# microsmt_pnpboard_v17_sheet_1.net
KiCad netlist of a schematic drawn in Altium Designer
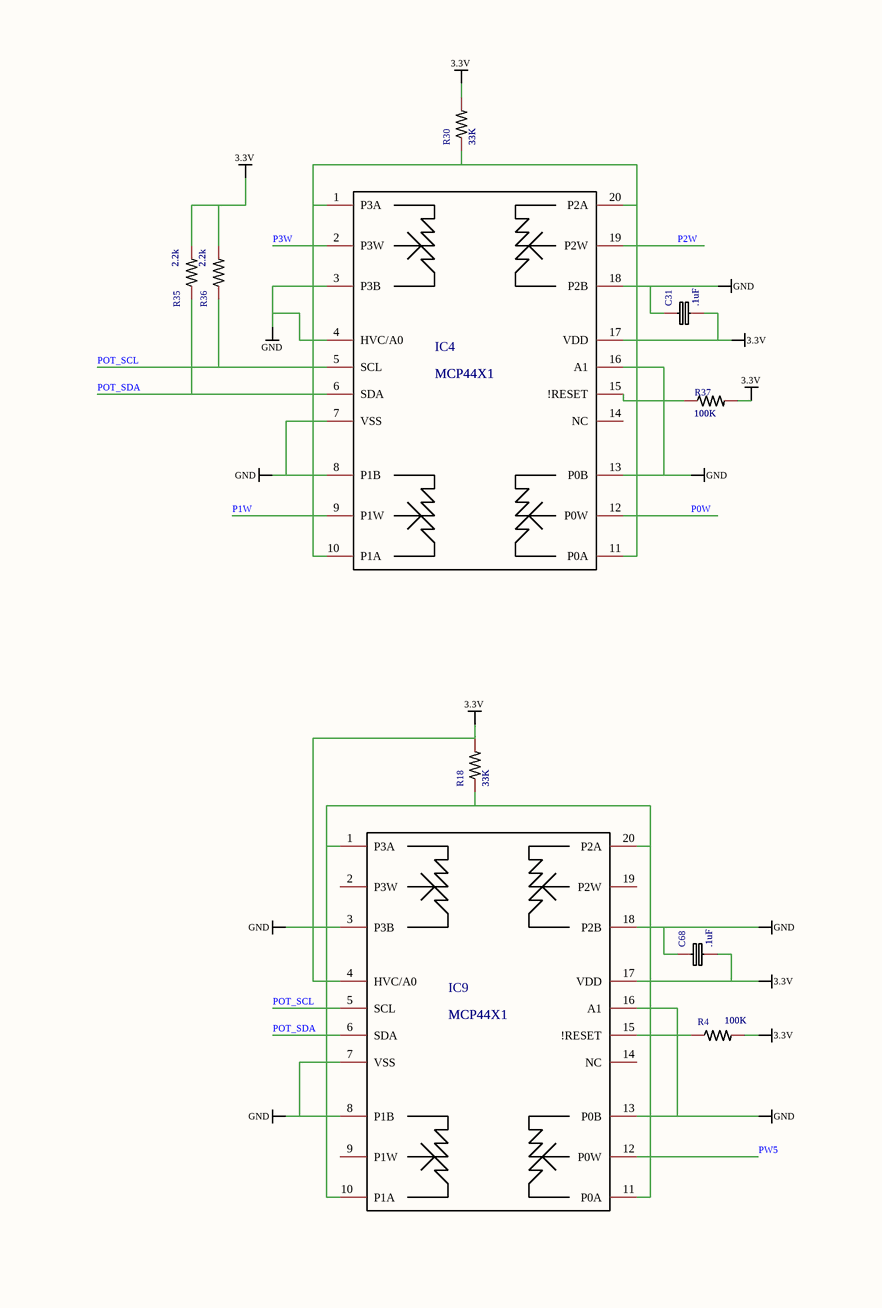
[diagram p0: microsmt_pnpboard_v17_sheet_1.schdoc, top middle]
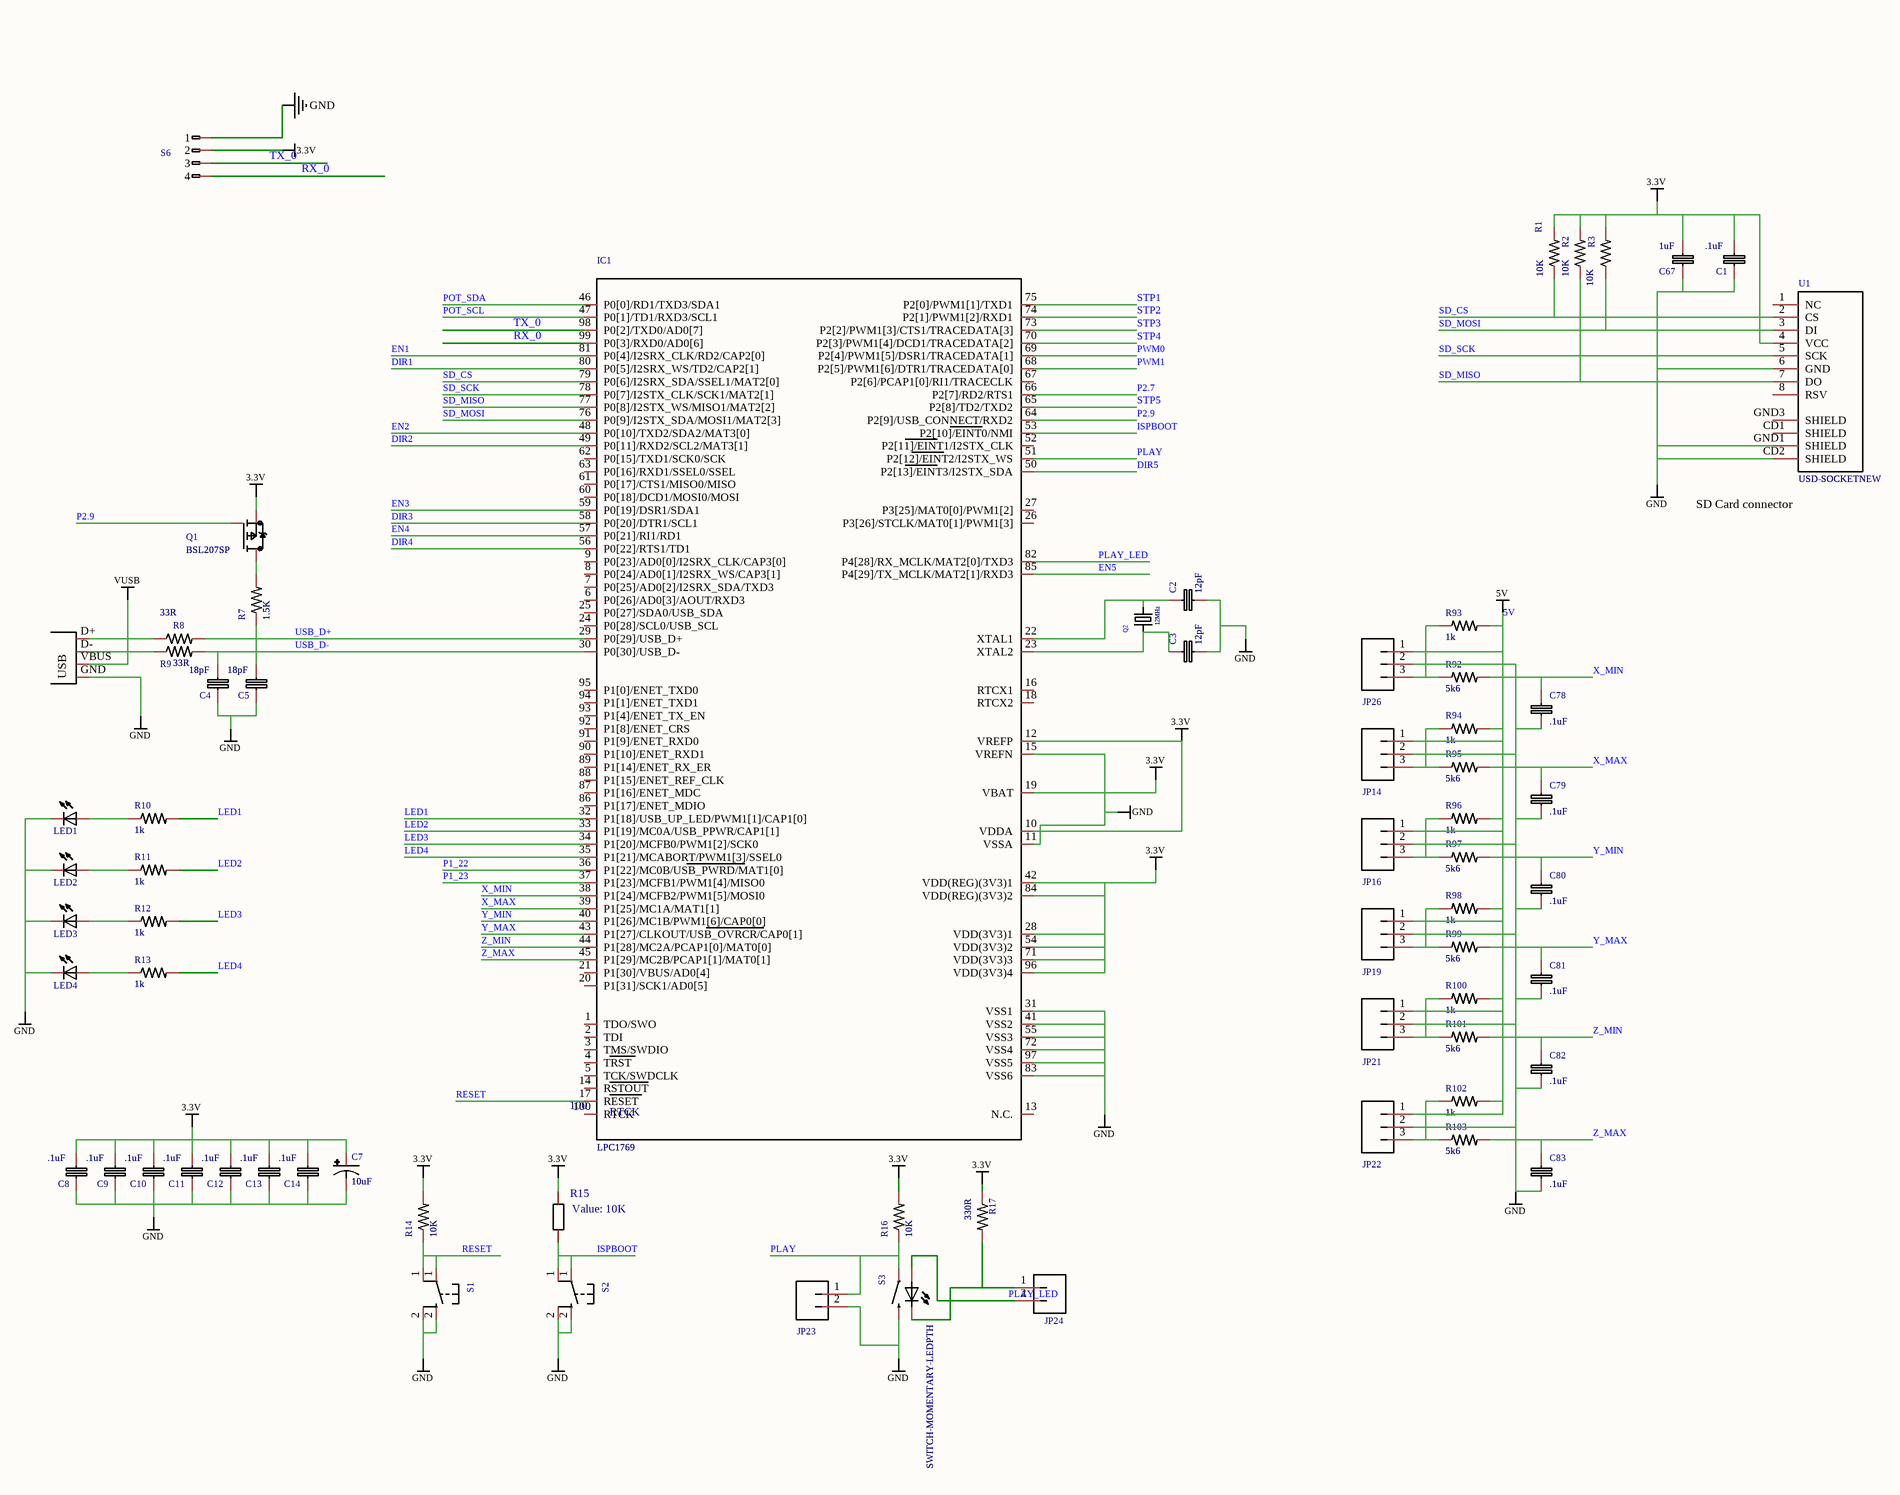
[diagram p1: microsmt_pnpboard_v17_sheet_1.schdoc, top right]
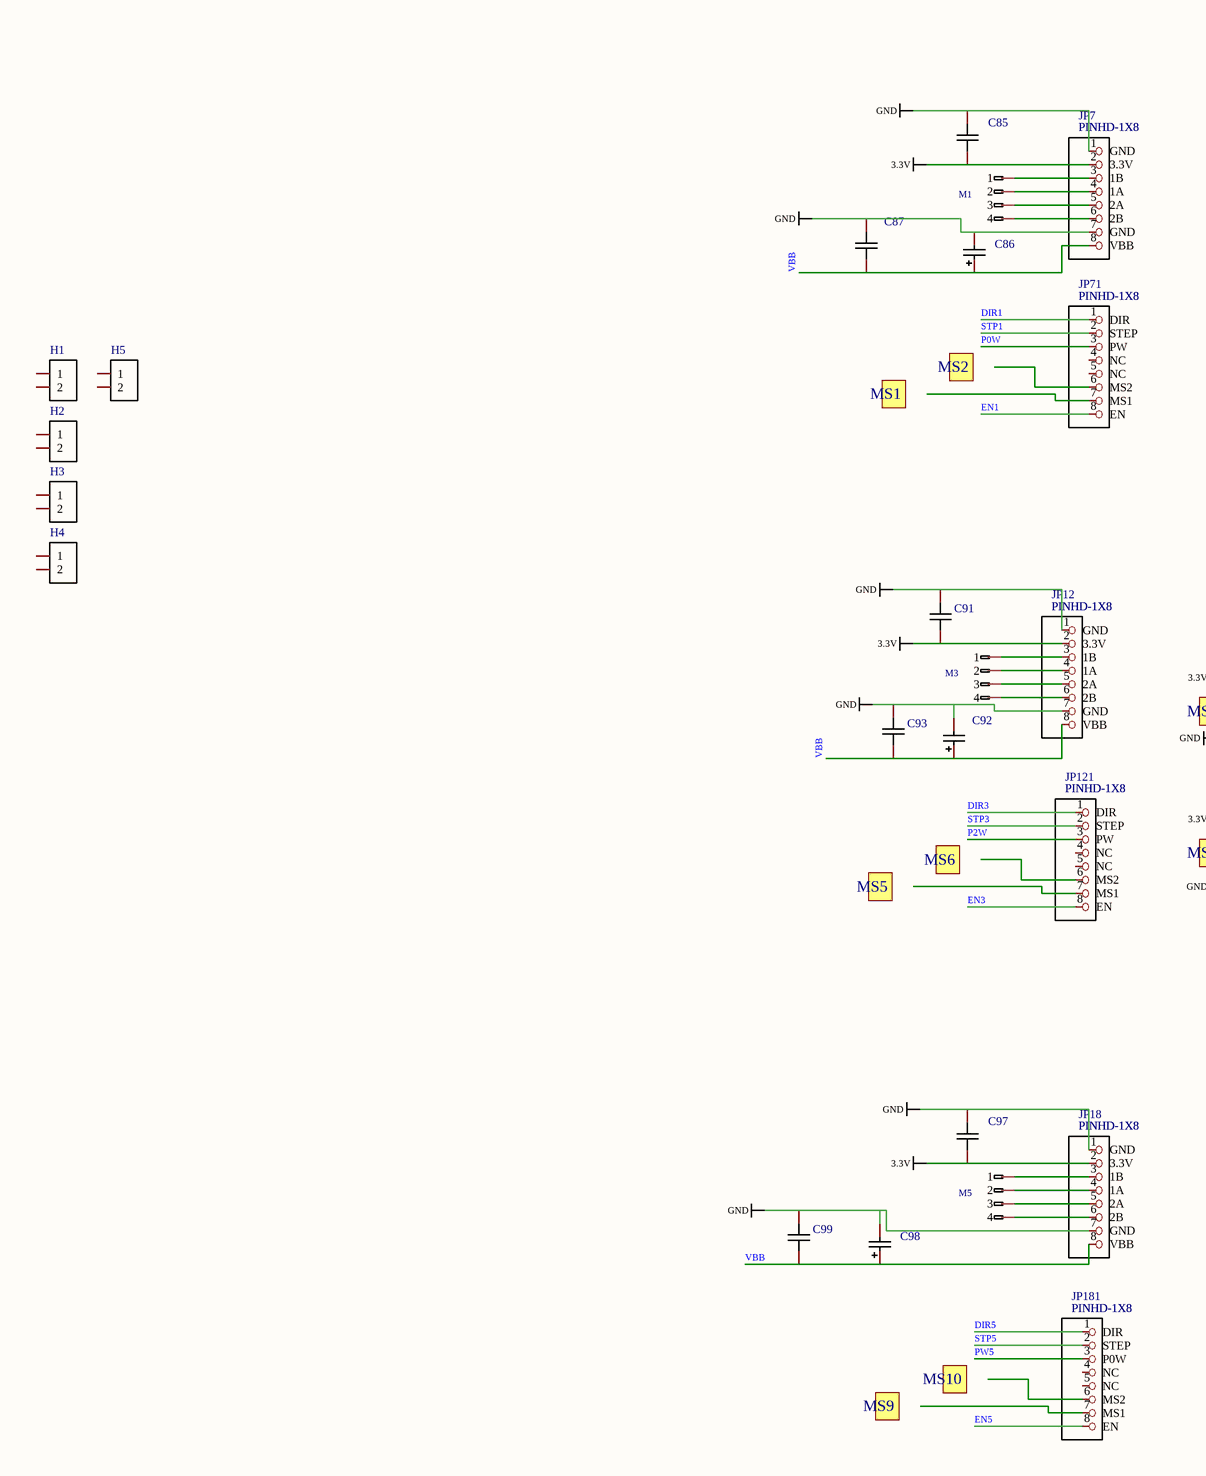
[diagram p2: microsmt_pnpboard_v17_sheet_1.schdoc, bottom left]
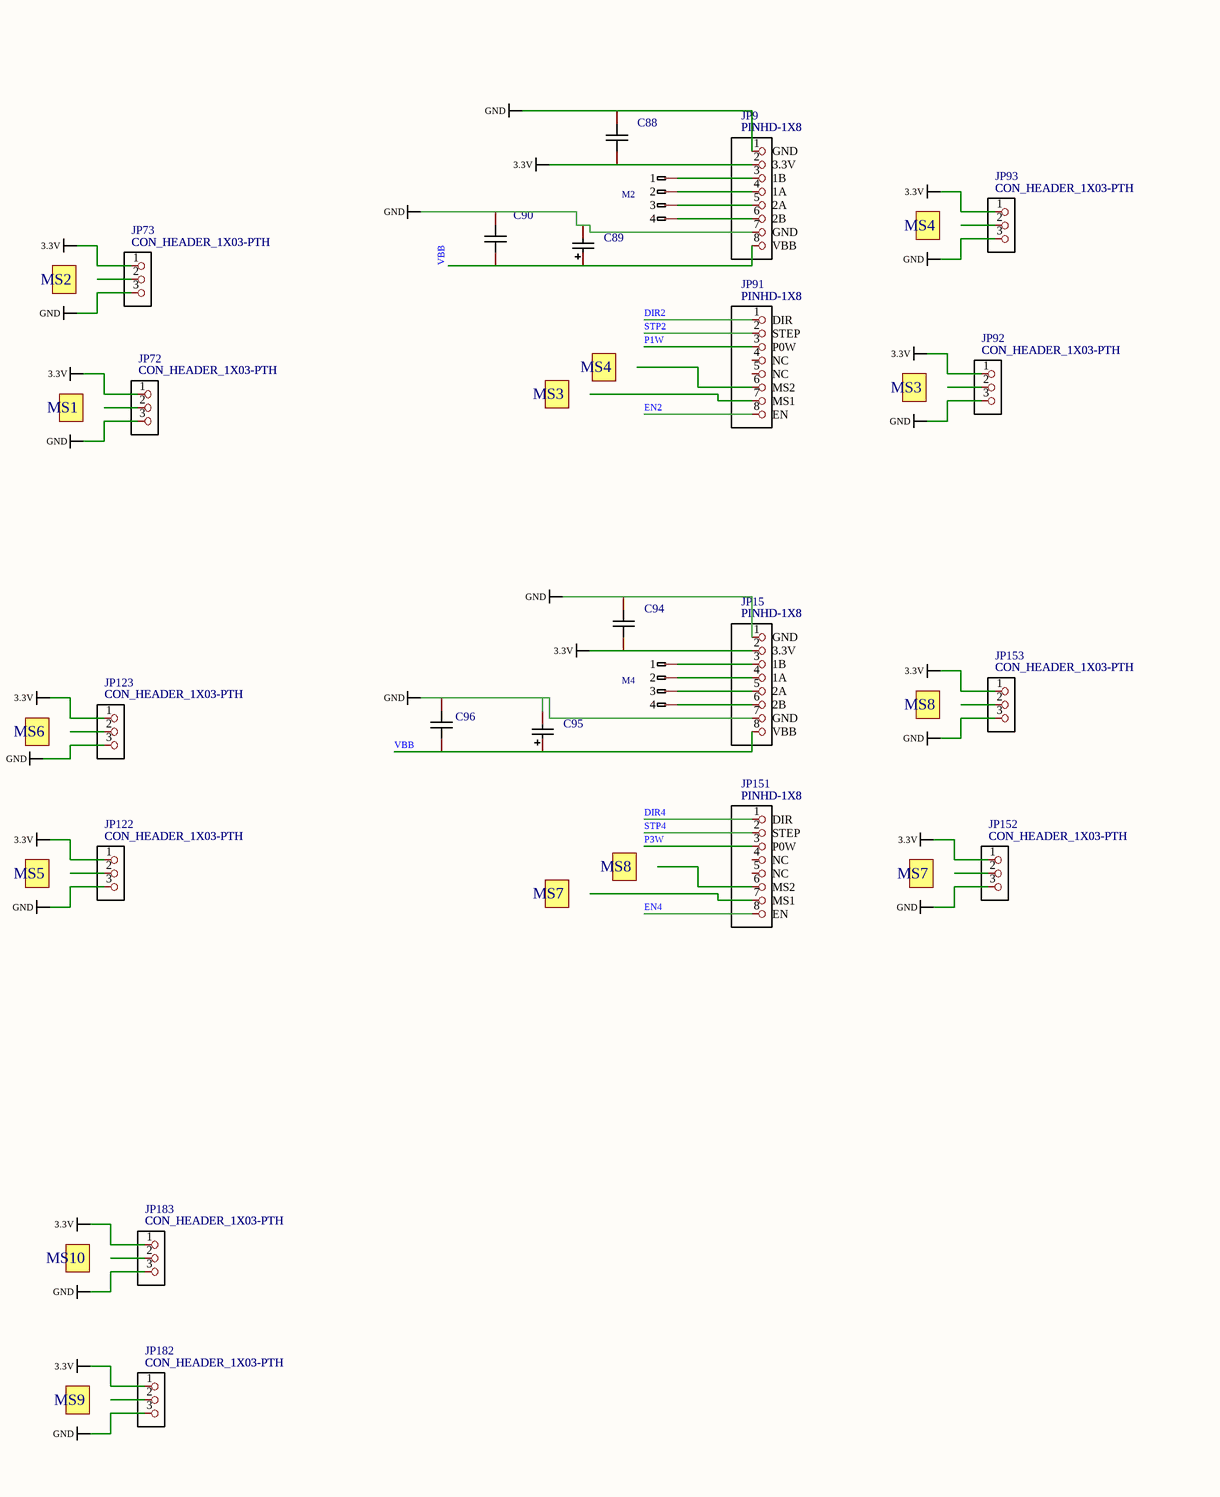
[diagram p3: microsmt_pnpboard_v17_sheet_1.schdoc, bottom middle]

(export (version "E")
  (design (tool "Eeschema 10.0.6"))
  (components
    (comp (ref "C1")
      (value ".1uF")
      (fields (field (name "NAME") ".1uF"))
      (libsource (lib "") (part "root_0_.1uF__2"))
    )
    (comp (ref "C2")
      (value "12pF")
      (fields (field (name "NAME") "12pF"))
      (libsource (lib "altium-import") (part "root_0_12pF_"))
    )
    (comp (ref "C3")
      (value "12pF")
      (fields (field (name "NAME") "12pF"))
      (libsource (lib "altium-import") (part "root_0_12pF_"))
    )
    (comp (ref "C4")
      (value "18pF")
      (fields (field (name "NAME") "18pF"))
      (libsource (lib "altium-import") (part "root_0_18pF_"))
    )
    (comp (ref "C5")
      (value "18pF")
      (fields (field (name "NAME") "18pF"))
      (libsource (lib "altium-import") (part "root_0_18pF_"))
    )
    (comp (ref "C7")
      (value "10uF")
      (fields (field (name "NAME") "10uF"))
      (libsource (lib "altium-import") (part "root_0_10uF_"))
    )
    (comp (ref "C8")
      (value ".1uF")
      (fields (field (name "NAME") ".1uF"))
      (libsource (lib "") (part "root_0_.1uF__1"))
    )
    (comp (ref "C9")
      (value ".1uF")
      (fields (field (name "NAME") ".1uF"))
      (libsource (lib "") (part "root_0_.1uF__1"))
    )
    (comp (ref "C10")
      (value ".1uF")
      (fields (field (name "NAME") ".1uF"))
      (libsource (lib "") (part "root_0_.1uF__1"))
    )
    (comp (ref "C11")
      (value ".1uF")
      (fields (field (name "NAME") ".1uF"))
      (libsource (lib "") (part "root_0_.1uF__1"))
    )
    (comp (ref "C12")
      (value ".1uF")
      (fields (field (name "NAME") ".1uF"))
      (libsource (lib "") (part "root_0_.1uF__1"))
    )
    (comp (ref "C13")
      (value ".1uF")
      (fields (field (name "NAME") ".1uF"))
      (libsource (lib "") (part "root_0_.1uF__1"))
    )
    (comp (ref "C14")
      (value ".1uF")
      (fields (field (name "NAME") ".1uF"))
      (libsource (lib "") (part "root_0_.1uF__1"))
    )
    (comp (ref "C31")
      (value ".1uF")
      (fields (field (name "NAME") ".1uF"))
      (libsource (lib "") (part "root_0_.1uF__3"))
    )
    (comp (ref "C67")
      (value "1uF")
      (fields (field (name "NAME") "1uF"))
      (libsource (lib "altium-import") (part "root_0_1uF_"))
    )
    (comp (ref "C68")
      (value ".1uF")
      (fields (field (name "NAME") ".1uF"))
      (libsource (lib "") (part "root_0_.1uF__3"))
    )
    (comp (ref "C78")
      (value ".1uF")
      (fields (field (name "NAME") ".1uF"))
      (libsource (lib "altium-import") (part "root_0_.1uF_"))
    )
    (comp (ref "C79")
      (value ".1uF")
      (fields (field (name "NAME") ".1uF"))
      (libsource (lib "altium-import") (part "root_0_.1uF_"))
    )
    (comp (ref "C80")
      (value ".1uF")
      (fields (field (name "NAME") ".1uF"))
      (libsource (lib "altium-import") (part "root_0_.1uF_"))
    )
    (comp (ref "C81")
      (value ".1uF")
      (fields (field (name "NAME") ".1uF"))
      (libsource (lib "altium-import") (part "root_0_.1uF_"))
    )
    (comp (ref "C82")
      (value ".1uF")
      (fields (field (name "NAME") ".1uF"))
      (libsource (lib "altium-import") (part "root_0_.1uF_"))
    )
    (comp (ref "C83")
      (value ".1uF")
      (fields (field (name "NAME") ".1uF"))
      (libsource (lib "altium-import") (part "root_0_.1uF_"))
    )
    (comp (ref "C85")
      (value "100nF")
      (description "容值:100nF;精度:±10%;额定电压:50V;温度系数:X7R;")
      (libsource (lib "altium-import") (part "root_1_CAP_0603_"))
    )
    (comp (ref "C86")
      (value "100uF")
      (description "容值:10uF;精度:±20%;额定电压:16V;电容体直径:-;电容体长度:-;纹波电流:-;等效串联电阻:-;工作寿命:2000hrs@85;工作温度:-40~+85;")
      (libsource (lib "altium-import") (part "root_3_C_Ele_SMD_3x5.4mm_"))
    )
    (comp (ref "C87")
      (value "100nF")
      (description "容值:100nF;精度:±10%;额定电压:50V;温度系数:X7R;")
      (libsource (lib "altium-import") (part "root_1_CAP_0603_"))
    )
    (comp (ref "C88")
      (value "100nF")
      (description "容值:100nF;精度:±10%;额定电压:50V;温度系数:X7R;")
      (libsource (lib "altium-import") (part "root_1_CAP_0603_"))
    )
    (comp (ref "C89")
      (value "100uF")
      (description "容值:10uF;精度:±20%;额定电压:16V;电容体直径:-;电容体长度:-;纹波电流:-;等效串联电阻:-;工作寿命:2000hrs@85;工作温度:-40~+85;")
      (libsource (lib "altium-import") (part "root_3_C_Ele_SMD_3x5.4mm_"))
    )
    (comp (ref "C90")
      (value "CAP_0603")
      (description "容值:100nF;精度:±10%;额定电压:50V;温度系数:X7R;")
      (libsource (lib "altium-import") (part "root_1_CAP_0603_"))
    )
    (comp (ref "C91")
      (value "CAP_0603")
      (description "容值:100nF;精度:±10%;额定电压:50V;温度系数:X7R;")
      (libsource (lib "altium-import") (part "root_1_CAP_0603_"))
    )
    (comp (ref "C92")
      (value "C_Ele_SMD_3x5.4mm")
      (description "容值:10uF;精度:±20%;额定电压:16V;电容体直径:-;电容体长度:-;纹波电流:-;等效串联电阻:-;工作寿命:2000hrs@85;工作温度:-40~+85;")
      (libsource (lib "altium-import") (part "root_3_C_Ele_SMD_3x5.4mm_"))
    )
    (comp (ref "C93")
      (value "100nF")
      (description "容值:100nF;精度:±10%;额定电压:50V;温度系数:X7R;")
      (libsource (lib "altium-import") (part "root_1_CAP_0603_"))
    )
    (comp (ref "C94")
      (value "100nF")
      (description "容值:100nF;精度:±10%;额定电压:50V;温度系数:X7R;")
      (libsource (lib "altium-import") (part "root_1_CAP_0603_"))
    )
    (comp (ref "C95")
      (value "100uF")
      (description "容值:10uF;精度:±20%;额定电压:16V;电容体直径:-;电容体长度:-;纹波电流:-;等效串联电阻:-;工作寿命:2000hrs@85;工作温度:-40~+85;")
      (libsource (lib "altium-import") (part "root_3_C_Ele_SMD_3x5.4mm_"))
    )
    (comp (ref "C96")
      (value "100nF")
      (description "容值:100nF;精度:±10%;额定电压:50V;温度系数:X7R;")
      (libsource (lib "altium-import") (part "root_1_CAP_0603_"))
    )
    (comp (ref "C97")
      (value "100nF")
      (description "容值:100nF;精度:±10%;额定电压:50V;温度系数:X7R;")
      (libsource (lib "altium-import") (part "root_1_CAP_0603_"))
    )
    (comp (ref "C98")
      (value "100uF")
      (description "容值:10uF;精度:±20%;额定电压:16V;电容体直径:-;电容体长度:-;纹波电流:-;等效串联电阻:-;工作寿命:2000hrs@85;工作温度:-40~+85;")
      (libsource (lib "altium-import") (part "root_3_C_Ele_SMD_3x5.4mm_"))
    )
    (comp (ref "C99")
      (value "100nF")
      (description "容值:100nF;精度:±10%;额定电压:50V;温度系数:X7R;")
      (libsource (lib "altium-import") (part "root_1_CAP_0603_"))
    )
    (comp (ref "H1")
      (value "HDR-F_2.54_1x2P")
      (libsource (lib "altium-import") (part "root_0_HDR-F_2.54_1x2P_"))
    )
    (comp (ref "H2")
      (value "HDR-F_2.54_1x2P")
      (libsource (lib "altium-import") (part "root_0_HDR-F_2.54_1x2P_"))
    )
    (comp (ref "H3")
      (value "HDR-F_2.54_1x2P")
      (libsource (lib "altium-import") (part "root_0_HDR-F_2.54_1x2P_"))
    )
    (comp (ref "H4")
      (value "HDR-F_2.54_1x2P")
      (libsource (lib "altium-import") (part "root_0_HDR-F_2.54_1x2P_"))
    )
    (comp (ref "H5")
      (value "HDR-F_2.54_1x2P")
      (libsource (lib "altium-import") (part "root_0_HDR-F_2.54_1x2P_"))
    )
    (comp (ref "IC1")
      (value "LPC1769")
      (fields (field (name "NAME") "LPC1769") (field (name "NAME_1") "RTCK") (field (name "NUMBER") "100"))
      (libsource (lib "altium-import") (part "root_0_LPC1769_"))
    )
    (comp (ref "IC4")
      (value "MCP44X1")
      (fields (field (name "NAME") "MCP44X1"))
      (libsource (lib "altium-import") (part "root_0_MCP44X1_"))
    )
    (comp (ref "IC9")
      (value "MCP44X1")
      (fields (field (name "NAME") "MCP44X1"))
      (libsource (lib "altium-import") (part "root_0_MCP44X1_"))
    )
    (comp (ref "JP7")
      (value "PINHD-1X8")
      (fields (field (name "NAME") "PINHD-1X8"))
      (libsource (lib "altium-import") (part "root_0_PINHD-1X8_"))
    )
    (comp (ref "JP9")
      (value "PINHD-1X8")
      (fields (field (name "NAME") "PINHD-1X8"))
      (libsource (lib "altium-import") (part "root_0_PINHD-1X8_"))
    )
    (comp (ref "JP12")
      (value "PINHD-1X8")
      (fields (field (name "NAME") "PINHD-1X8"))
      (libsource (lib "altium-import") (part "root_0_PINHD-1X8_"))
    )
    (comp (ref "JP14") (value "M03POLAR") (libsource (lib "altium-import") (part "root_0_M03POLAR_")))
    (comp (ref "JP15")
      (value "PINHD-1X8")
      (fields (field (name "NAME") "PINHD-1X8"))
      (libsource (lib "altium-import") (part "root_0_PINHD-1X8_"))
    )
    (comp (ref "JP16") (value "M03POLAR") (libsource (lib "altium-import") (part "root_0_M03POLAR_")))
    (comp (ref "JP18")
      (value "PINHD-1X8")
      (fields (field (name "NAME") "PINHD-1X8"))
      (libsource (lib "altium-import") (part "root_0_PINHD-1X8_"))
    )
    (comp (ref "JP19") (value "M03POLAR") (libsource (lib "altium-import") (part "root_0_M03POLAR_")))
    (comp (ref "JP21") (value "M03POLAR") (libsource (lib "altium-import") (part "root_0_M03POLAR_")))
    (comp (ref "JP22") (value "M03POLAR") (libsource (lib "altium-import") (part "root_0_M03POLAR_")))
    (comp (ref "JP23") (value "M02PTH") (libsource (lib "") (part "root_0_M02PTH__1")))
    (comp (ref "JP24") (value "M02PTH") (libsource (lib "altium-import") (part "root_0_M02PTH_")))
    (comp (ref "JP26") (value "M03POLAR") (libsource (lib "altium-import") (part "root_0_M03POLAR_")))
    (comp (ref "JP71")
      (value "PINHD-1X8")
      (fields (field (name "NAME") "PINHD-1X8"))
      (libsource (lib "altium-import") (part "root_0_PINHD-1X8_"))
    )
    (comp (ref "JP72")
      (value "CON_HEADER_1X03-PTH")
      (fields (field (name "NAME") "CON_HEADER_1X03-PTH"))
      (libsource (lib "altium-import") (part "root_0_CON_HEADER_1X03-PTH_"))
    )
    (comp (ref "JP73")
      (value "CON_HEADER_1X03-PTH")
      (fields (field (name "NAME") "CON_HEADER_1X03-PTH"))
      (libsource (lib "altium-import") (part "root_0_CON_HEADER_1X03-PTH_"))
    )
    (comp (ref "JP91")
      (value "PINHD-1X8")
      (fields (field (name "NAME") "PINHD-1X8"))
      (libsource (lib "altium-import") (part "root_0_PINHD-1X8_"))
    )
    (comp (ref "JP92")
      (value "CON_HEADER_1X03-PTH")
      (fields (field (name "NAME") "CON_HEADER_1X03-PTH"))
      (libsource (lib "altium-import") (part "root_0_CON_HEADER_1X03-PTH_"))
    )
    (comp (ref "JP93")
      (value "CON_HEADER_1X03-PTH")
      (fields (field (name "NAME") "CON_HEADER_1X03-PTH"))
      (libsource (lib "altium-import") (part "root_0_CON_HEADER_1X03-PTH_"))
    )
    (comp (ref "JP121")
      (value "PINHD-1X8")
      (fields (field (name "NAME") "PINHD-1X8"))
      (libsource (lib "altium-import") (part "root_0_PINHD-1X8_"))
    )
    (comp (ref "JP122")
      (value "CON_HEADER_1X03-PTH")
      (fields (field (name "NAME") "CON_HEADER_1X03-PTH"))
      (libsource (lib "altium-import") (part "root_0_CON_HEADER_1X03-PTH_"))
    )
    (comp (ref "JP123")
      (value "CON_HEADER_1X03-PTH")
      (fields (field (name "NAME") "CON_HEADER_1X03-PTH"))
      (libsource (lib "altium-import") (part "root_0_CON_HEADER_1X03-PTH_"))
    )
    (comp (ref "JP151")
      (value "PINHD-1X8")
      (fields (field (name "NAME") "PINHD-1X8"))
      (libsource (lib "altium-import") (part "root_0_PINHD-1X8_"))
    )
    (comp (ref "JP152")
      (value "CON_HEADER_1X03-PTH")
      (fields (field (name "NAME") "CON_HEADER_1X03-PTH"))
      (libsource (lib "altium-import") (part "root_0_CON_HEADER_1X03-PTH_"))
    )
    (comp (ref "JP153")
      (value "CON_HEADER_1X03-PTH")
      (fields (field (name "NAME") "CON_HEADER_1X03-PTH"))
      (libsource (lib "altium-import") (part "root_0_CON_HEADER_1X03-PTH_"))
    )
    (comp (ref "JP181")
      (value "PINHD-1X8")
      (fields (field (name "NAME") "PINHD-1X8"))
      (libsource (lib "altium-import") (part "root_0_PINHD-1X8_"))
    )
    (comp (ref "JP182")
      (value "CON_HEADER_1X03-PTH")
      (fields (field (name "NAME") "CON_HEADER_1X03-PTH"))
      (libsource (lib "altium-import") (part "root_0_CON_HEADER_1X03-PTH_"))
    )
    (comp (ref "JP183")
      (value "CON_HEADER_1X03-PTH")
      (fields (field (name "NAME") "CON_HEADER_1X03-PTH"))
      (libsource (lib "altium-import") (part "root_0_CON_HEADER_1X03-PTH_"))
    )
    (comp (ref "LED1")
      (value "LEDCHIP-LED0805")
      (libsource (lib "altium-import") (part "root_0_LEDCHIP-LED0805_"))
    )
    (comp (ref "LED2")
      (value "LEDCHIP-LED0805")
      (libsource (lib "altium-import") (part "root_0_LEDCHIP-LED0805_"))
    )
    (comp (ref "LED3")
      (value "LEDCHIP-LED0805")
      (libsource (lib "altium-import") (part "root_0_LEDCHIP-LED0805_"))
    )
    (comp (ref "LED4")
      (value "LEDCHIP-LED0805")
      (libsource (lib "altium-import") (part "root_0_LEDCHIP-LED0805_"))
    )
    (comp (ref "M1") (value "10X04MTA") (libsource (lib "altium-import") (part "root_0_10X04MTA_")))
    (comp (ref "M2") (value "10X04MTA") (libsource (lib "altium-import") (part "root_0_10X04MTA_")))
    (comp (ref "M3") (value "10X04MTA") (libsource (lib "altium-import") (part "root_0_10X04MTA_")))
    (comp (ref "M4") (value "10X04MTA") (libsource (lib "altium-import") (part "root_0_10X04MTA_")))
    (comp (ref "M5") (value "10X04MTA") (libsource (lib "altium-import") (part "root_0_10X04MTA_")))
    (comp (ref "Q1")
      (value "BSL207SP")
      (fields (field (name "NAME") "BSL207SP"))
      (libsource (lib "altium-import") (part "root_0_BSL207SP_"))
    )
    (comp (ref "Q2")
      (value "12MHz")
      (fields (field (name "NAME") "12MHz"))
      (libsource (lib "altium-import") (part "root_0_12MHz_"))
    )
    (comp (ref "R1")
      (value "10K")
      (fields (field (name "NAME") "10K"))
      (libsource (lib "altium-import") (part "root_0_10K_"))
    )
    (comp (ref "R2")
      (value "10K")
      (fields (field (name "NAME") "10K"))
      (libsource (lib "altium-import") (part "root_0_10K_"))
    )
    (comp (ref "R3")
      (value "10K")
      (fields (field (name "NAME") "10K"))
      (libsource (lib "altium-import") (part "root_0_10K_"))
    )
    (comp (ref "R4")
      (value "100K")
      (fields (field (name "NAME") "100K"))
      (libsource (lib "altium-import") (part "root_0_100K_"))
    )
    (comp (ref "R7")
      (value "1.5K")
      (fields (field (name "NAME") "1.5K"))
      (libsource (lib "altium-import") (part "root_0_1.5K_"))
    )
    (comp (ref "R8")
      (value "33R")
      (fields (field (name "NAME") "33R"))
      (libsource (lib "altium-import") (part "root_0_33R_"))
    )
    (comp (ref "R9")
      (value "33R")
      (fields (field (name "NAME") "33R"))
      (libsource (lib "altium-import") (part "root_0_33R_"))
    )
    (comp (ref "R10")
      (value "1k")
      (fields (field (name "NAME") "1k"))
      (libsource (lib "altium-import") (part "root_0_1k_"))
    )
    (comp (ref "R11")
      (value "1k")
      (fields (field (name "NAME") "1k"))
      (libsource (lib "altium-import") (part "root_0_1k_"))
    )
    (comp (ref "R12")
      (value "1k")
      (fields (field (name "NAME") "1k"))
      (libsource (lib "altium-import") (part "root_0_1k_"))
    )
    (comp (ref "R13")
      (value "1k")
      (fields (field (name "NAME") "1k"))
      (libsource (lib "altium-import") (part "root_0_1k_"))
    )
    (comp (ref "R14")
      (value "10K")
      (fields (field (name "NAME") "10K"))
      (libsource (lib "altium-import") (part "root_0_10K_"))
    )
    (comp (ref "R15")
      (value "10K")
      (fields (field (name "Comment") "Res_0603"))
      (libsource (lib "altium-import") (part "root_1_Res_0603_"))
    )
    (comp (ref "R16")
      (value "10K")
      (fields (field (name "NAME") "10K"))
      (libsource (lib "altium-import") (part "root_0_10K_"))
    )
    (comp (ref "R17")
      (value "330R")
      (fields (field (name "NAME") "330R"))
      (libsource (lib "altium-import") (part "root_0_330R_"))
    )
    (comp (ref "R18")
      (value "33K")
      (fields (field (name "NAME") "33K"))
      (libsource (lib "altium-import") (part "root_0_33K_"))
    )
    (comp (ref "R30")
      (value "33K")
      (fields (field (name "NAME") "33K"))
      (libsource (lib "altium-import") (part "root_0_33K_"))
    )
    (comp (ref "R35")
      (value "2.2k")
      (fields (field (name "NAME") "2.2k"))
      (libsource (lib "altium-import") (part "root_0_2.2k_"))
    )
    (comp (ref "R36")
      (value "2.2k")
      (fields (field (name "NAME") "2.2k"))
      (libsource (lib "altium-import") (part "root_0_2.2k_"))
    )
    (comp (ref "R37")
      (value "100K")
      (fields (field (name "NAME") "100K"))
      (libsource (lib "altium-import") (part "root_3_100K_"))
    )
    (comp (ref "R92")
      (value "5k6")
      (fields (field (name "NAME") "5k6"))
      (libsource (lib "altium-import") (part "root_0_5k6_"))
    )
    (comp (ref "R93")
      (value "1k")
      (fields (field (name "NAME") "1k"))
      (libsource (lib "altium-import") (part "root_0_1k_"))
    )
    (comp (ref "R94")
      (value "1k")
      (fields (field (name "NAME") "1k"))
      (libsource (lib "altium-import") (part "root_0_1k_"))
    )
    (comp (ref "R95")
      (value "5k6")
      (fields (field (name "NAME") "5k6"))
      (libsource (lib "altium-import") (part "root_0_5k6_"))
    )
    (comp (ref "R96")
      (value "1k")
      (fields (field (name "NAME") "1k"))
      (libsource (lib "altium-import") (part "root_0_1k_"))
    )
    (comp (ref "R97")
      (value "5k6")
      (fields (field (name "NAME") "5k6"))
      (libsource (lib "altium-import") (part "root_0_5k6_"))
    )
    (comp (ref "R98")
      (value "1k")
      (fields (field (name "NAME") "1k"))
      (libsource (lib "altium-import") (part "root_0_1k_"))
    )
    (comp (ref "R99")
      (value "5k6")
      (fields (field (name "NAME") "5k6"))
      (libsource (lib "altium-import") (part "root_0_5k6_"))
    )
    (comp (ref "R100")
      (value "1k")
      (fields (field (name "NAME") "1k"))
      (libsource (lib "altium-import") (part "root_0_1k_"))
    )
    (comp (ref "R101")
      (value "5k6")
      (fields (field (name "NAME") "5k6"))
      (libsource (lib "altium-import") (part "root_0_5k6_"))
    )
    (comp (ref "R102")
      (value "1k")
      (fields (field (name "NAME") "1k"))
      (libsource (lib "altium-import") (part "root_0_1k_"))
    )
    (comp (ref "R103")
      (value "5k6")
      (fields (field (name "NAME") "5k6"))
      (libsource (lib "altium-import") (part "root_0_5k6_"))
    )
    (comp (ref "S1") (value "TAC_SWITCHSMD") (libsource (lib "altium-import") (part "root_0_TAC_SWITCHSMD_")))
    (comp (ref "S2") (value "TAC_SWITCHSMD") (libsource (lib "altium-import") (part "root_0_TAC_SWITCHSMD_")))
    (comp (ref "S3")
      (value "SWITCH-MOMENTARY-LEDPTH")
      (fields (field (name "NAME") "SWITCH-MOMENTARY-LEDPTH"))
      (libsource (lib "altium-import") (part "root_0_SWITCH-MOMENTARY-LEDPTH_"))
    )
    (comp (ref "S6") (value "10X04MTA") (libsource (lib "altium-import") (part "root_0_10X04MTA_")))
    (comp (ref "U1")
      (value "USD-SOCKETNEW")
      (fields (field (name "NAME") "USD-SOCKETNEW"))
      (libsource (lib "altium-import") (part "root_0_USD-SOCKETNEW_"))
    )
    (comp (ref "X14") (value "USBPTH") (libsource (lib "altium-import") (part "root_0_USBPTH_")))
  )
  (nets
    (net (code "1") (name "/DIR1") (class "Default")
      (node (ref "IC1") (pin "80") (pinfunction "P0[5]/I2SRX_WS/TD2/CAP2[1]_80") (pintype "passive"))
      (node (ref "JP71") (pin "1") (pinfunction "GND_1") (pintype "passive"))
    )
    (net (code "2") (name "/DIR2") (class "Default")
      (node (ref "IC1") (pin "49") (pinfunction "P0[11]/RXD2/SCL2/MAT3[1]_49") (pintype "passive"))
      (node (ref "JP91") (pin "1") (pinfunction "GND_1") (pintype "passive"))
    )
    (net (code "3") (name "/DIR3") (class "Default")
      (node (ref "IC1") (pin "58") (pinfunction "P0[20]/DTR1/SCL1_58") (pintype "passive"))
      (node (ref "JP121") (pin "1") (pinfunction "GND_1") (pintype "passive"))
    )
    (net (code "4") (name "/DIR4") (class "Default")
      (node (ref "IC1") (pin "56") (pinfunction "P0[22]/RTS1/TD1_56") (pintype "passive"))
      (node (ref "JP151") (pin "1") (pinfunction "GND_1") (pintype "passive"))
    )
    (net (code "5") (name "/DIR5") (class "Default")
      (node (ref "IC1") (pin "50") (pinfunction "P2[13]/EINT3/I2STX_SDA_50") (pintype "passive"))
      (node (ref "JP181") (pin "1") (pinfunction "GND_1") (pintype "passive"))
    )
    (net (code "6") (name "/EN1") (class "Default")
      (node (ref "IC1") (pin "81") (pinfunction "P0[4]/I2SRX_CLK/RD2/CAP2[0]_81") (pintype "passive"))
      (node (ref "JP71") (pin "8") (pinfunction "VBB_8") (pintype "passive"))
    )
    (net (code "7") (name "/EN2") (class "Default")
      (node (ref "IC1") (pin "48") (pinfunction "P0[10]/TXD2/SDA2/MAT3[0]_48") (pintype "passive"))
      (node (ref "JP91") (pin "8") (pinfunction "VBB_8") (pintype "passive"))
    )
    (net (code "8") (name "/EN3") (class "Default")
      (node (ref "IC1") (pin "59") (pinfunction "P0[19]/DSR1/SDA1_59") (pintype "passive"))
      (node (ref "JP121") (pin "8") (pinfunction "VBB_8") (pintype "passive"))
    )
    (net (code "9") (name "/EN4") (class "Default")
      (node (ref "IC1") (pin "57") (pinfunction "P0[21]/RI1/RD1_57") (pintype "passive"))
      (node (ref "JP151") (pin "8") (pinfunction "VBB_8") (pintype "passive"))
    )
    (net (code "10") (name "/EN5") (class "Default")
      (node (ref "IC1") (pin "85") (pinfunction "P4[29]/TX_MCLK/MAT2[1]/RXD3_85") (pintype "passive"))
      (node (ref "JP181") (pin "8") (pinfunction "VBB_8") (pintype "passive"))
    )
    (net (code "11") (name "/ISPBOOT") (class "Default")
      (node (ref "IC1") (pin "53") (pinfunction "P2[10]/EINT0/NMI_53") (pintype "passive"))
      (node (ref "R15") (pin "1") (pinfunction "1_1") (pintype "passive"))
      (node (ref "S2") (pin "1") (pinfunction "1_1") (pintype "passive"))
    )
    (net (code "12") (name "/LED1") (class "Default")
      (node (ref "IC1") (pin "32") (pinfunction "P1[18]/USB_UP_LED/PWM1[1]/CAP1[0]_32") (pintype "passive"))
      (node (ref "R10") (pin "2") (pinfunction "2_2") (pintype "passive"))
    )
    (net (code "13") (name "/LED2") (class "Default")
      (node (ref "IC1") (pin "33") (pinfunction "P1[19]/MC0A/USB_PPWR/CAP1[1]_33") (pintype "passive"))
      (node (ref "R11") (pin "2") (pinfunction "2_2") (pintype "passive"))
    )
    (net (code "14") (name "/LED3") (class "Default")
      (node (ref "IC1") (pin "34") (pinfunction "P1[20]/MCFB0/PWM1[2]/SCK0_34") (pintype "passive"))
      (node (ref "R12") (pin "2") (pinfunction "2_2") (pintype "passive"))
    )
    (net (code "15") (name "/LED4") (class "Default")
      (node (ref "IC1") (pin "35") (pinfunction "P1[21]/MCABORT/PWM1[3]/SSEL0_35") (pintype "passive"))
      (node (ref "R13") (pin "2") (pinfunction "2_2") (pintype "passive"))
    )
    (net (code "26") (name "/P0W") (class "Default")
      (node (ref "IC4") (pin "12") (pinfunction "P0W_12") (pintype "passive"))
      (node (ref "JP71") (pin "3") (pinfunction "1B_3") (pintype "passive"))
    )
    (net (code "27") (name "/P1W") (class "Default")
      (node (ref "IC4") (pin "9") (pinfunction "P1W_9") (pintype "passive"))
      (node (ref "JP91") (pin "3") (pinfunction "1B_3") (pintype "passive"))
    )
    (net (code "28") (name "/P1_22") (class "Default")
      (node (ref "IC1") (pin "36") (pinfunction "P1[22]/MC0B/USB_PWRD/MAT1[0]_36") (pintype "passive"))
    )
    (net (code "29") (name "/P1_23") (class "Default")
      (node (ref "IC1") (pin "37") (pinfunction "P1[23]/MCFB1/PWM1[4]/MISO0_37") (pintype "passive"))
    )
    (net (code "30") (name "/P2.7") (class "Default")
      (node (ref "IC1") (pin "66") (pinfunction "P2[7]/RD2/RTS1_66") (pintype "passive"))
    )
    (net (code "31") (name "/P2.9") (class "Default")
      (node (ref "IC1") (pin "64") (pinfunction "P2[9]/USB_CONNECT/RXD2_64") (pintype "passive"))
      (node (ref "Q1") (pin "3") (pinfunction "G_3") (pintype "passive"))
    )
    (net (code "32") (name "/P2W") (class "Default")
      (node (ref "IC4") (pin "19") (pinfunction "P2W_19") (pintype "passive"))
      (node (ref "JP121") (pin "3") (pinfunction "1B_3") (pintype "passive"))
    )
    (net (code "33") (name "/P3W") (class "Default")
      (node (ref "IC4") (pin "2") (pinfunction "P3W_2") (pintype "passive"))
      (node (ref "JP151") (pin "3") (pinfunction "1B_3") (pintype "passive"))
    )
    (net (code "34") (name "/PLAY") (class "Default")
      (node (ref "IC1") (pin "51") (pinfunction "P2[12]/EINT2/I2STX_WS_51") (pintype "passive"))
      (node (ref "JP23") (pin "1") (pinfunction "1_1") (pintype "passive"))
      (node (ref "R16") (pin "1") (pinfunction "1_1") (pintype "passive"))
      (node (ref "S3") (pin "4") (pinfunction "1_4") (pintype "passive"))
    )
    (net (code "35") (name "/PLAY_LED") (class "Default")
      (node (ref "IC1") (pin "82") (pinfunction "P4[28]/RX_MCLK/MAT2[0]/TXD3_82") (pintype "passive"))
      (node (ref "JP24") (pin "2") (pinfunction "2_2") (pintype "passive"))
      (node (ref "S3") (pin "A") (pinfunction "A_A") (pintype "passive"))
    )
    (net (code "36") (name "/POT_SCL") (class "Default")
      (node (ref "IC1") (pin "47") (pinfunction "P0[1]/TD1/RXD3/SCL1_47") (pintype "passive"))
      (node (ref "IC4") (pin "5") (pinfunction "SCL_5") (pintype "passive"))
      (node (ref "IC9") (pin "5") (pinfunction "SCL_5") (pintype "passive"))
      (node (ref "R36") (pin "1") (pinfunction "1_1") (pintype "passive"))
    )
    (net (code "37") (name "/POT_SDA") (class "Default")
      (node (ref "IC1") (pin "46") (pinfunction "P0[0]/RD1/TXD3/SDA1_46") (pintype "passive"))
      (node (ref "IC4") (pin "6") (pinfunction "SDA_6") (pintype "passive"))
      (node (ref "IC9") (pin "6") (pinfunction "SDA_6") (pintype "passive"))
      (node (ref "R35") (pin "1") (pinfunction "1_1") (pintype "passive"))
    )
    (net (code "38") (name "/PW5") (class "Default")
      (node (ref "IC9") (pin "12") (pinfunction "P0W_12") (pintype "passive"))
      (node (ref "JP181") (pin "3") (pinfunction "1B_3") (pintype "passive"))
    )
    (net (code "39") (name "/PWM0") (class "Default")
      (node (ref "IC1") (pin "69") (pinfunction "P2[4]/PWM1[5]/DSR1/TRACEDATA[1]_69") (pintype "passive"))
    )
    (net (code "40") (name "/PWM1") (class "Default")
      (node (ref "IC1") (pin "68") (pinfunction "P2[5]/PWM1[6]/DTR1/TRACEDATA[0]_68") (pintype "passive"))
    )
    (net (code "41") (name "/RESET") (class "Default")
      (node (ref "IC1") (pin "17") (pinfunction "RESET_17") (pintype "passive"))
      (node (ref "R14") (pin "1") (pinfunction "1_1") (pintype "passive"))
      (node (ref "S1") (pin "1") (pinfunction "1_1") (pintype "passive"))
    )
    (net (code "42") (name "/RX_0") (class "Default")
      (node (ref "IC1") (pin "99") (pinfunction "P0[3]/RXD0/AD0[6]_99") (pintype "passive"))
      (node (ref "S6") (pin "4") (pinfunction "4_4") (pintype "passive"))
    )
    (net (code "43") (name "/SD_CS") (class "Default")
      (node (ref "IC1") (pin "79") (pinfunction "P0[6]/I2SRX_SDA/SSEL1/MAT2[0]_79") (pintype "passive"))
      (node (ref "R1") (pin "1") (pinfunction "1_1") (pintype "passive"))
      (node (ref "U1") (pin "2") (pinfunction "CS_2") (pintype "passive"))
    )
    (net (code "44") (name "/SD_MISO") (class "Default")
      (node (ref "IC1") (pin "77") (pinfunction "P0[8]/I2STX_WS/MISO1/MAT2[2]_77") (pintype "passive"))
      (node (ref "R2") (pin "1") (pinfunction "1_1") (pintype "passive"))
      (node (ref "U1") (pin "7") (pinfunction "DO_7") (pintype "passive"))
    )
    (net (code "45") (name "/SD_MOSI") (class "Default")
      (node (ref "IC1") (pin "76") (pinfunction "P0[9]/I2STX_SDA/MOSI1/MAT2[3]_76") (pintype "passive"))
      (node (ref "R3") (pin "1") (pinfunction "1_1") (pintype "passive"))
      (node (ref "U1") (pin "3") (pinfunction "DI_3") (pintype "passive"))
    )
    (net (code "46") (name "/SD_SCK") (class "Default")
      (node (ref "IC1") (pin "78") (pinfunction "P0[7]/I2STX_CLK/SCK1/MAT2[1]_78") (pintype "passive"))
      (node (ref "U1") (pin "5") (pinfunction "SCK_5") (pintype "passive"))
    )
    (net (code "47") (name "/STP1") (class "Default")
      (node (ref "IC1") (pin "75") (pinfunction "P2[0]/PWM1[1]/TXD1_75") (pintype "passive"))
      (node (ref "JP71") (pin "2") (pinfunction "3.3V_2") (pintype "passive"))
    )
    (net (code "48") (name "/STP2") (class "Default")
      (node (ref "IC1") (pin "74") (pinfunction "P2[1]/PWM1[2]/RXD1_74") (pintype "passive"))
      (node (ref "JP91") (pin "2") (pinfunction "3.3V_2") (pintype "passive"))
    )
    (net (code "49") (name "/STP3") (class "Default")
      (node (ref "IC1") (pin "73") (pinfunction "P2[2]/PWM1[3]/CTS1/TRACEDATA[3]_73") (pintype "passive"))
      (node (ref "JP121") (pin "2") (pinfunction "3.3V_2") (pintype "passive"))
    )
    (net (code "50") (name "/STP4") (class "Default")
      (node (ref "IC1") (pin "70") (pinfunction "P2[3]/PWM1[4]/DCD1/TRACEDATA[2]_70") (pintype "passive"))
      (node (ref "JP151") (pin "2") (pinfunction "3.3V_2") (pintype "passive"))
    )
    (net (code "51") (name "/STP5") (class "Default")
      (node (ref "IC1") (pin "65") (pinfunction "P2[8]/TD2/TXD2_65") (pintype "passive"))
      (node (ref "JP181") (pin "2") (pinfunction "3.3V_2") (pintype "passive"))
    )
    (net (code "52") (name "/TX_0") (class "Default")
      (node (ref "IC1") (pin "98") (pinfunction "P0[2]/TXD0/AD0[7]_98") (pintype "passive"))
      (node (ref "S6") (pin "3") (pinfunction "3_3") (pintype "passive"))
    )
    (net (code "53") (name "/USB_D+") (class "Default")
      (node (ref "C5") (pin "2") (pinfunction "2_2") (pintype "passive"))
      (node (ref "IC1") (pin "29") (pinfunction "P0[29]/USB_D+_29") (pintype "passive"))
      (node (ref "R7") (pin "1") (pinfunction "1_1") (pintype "passive"))
      (node (ref "R8") (pin "2") (pinfunction "2_2") (pintype "passive"))
    )
    (net (code "54") (name "/USB_D-") (class "Default")
      (node (ref "C4") (pin "2") (pinfunction "2_2") (pintype "passive"))
      (node (ref "IC1") (pin "30") (pinfunction "P0[30]/USB_D-_30") (pintype "passive"))
      (node (ref "R9") (pin "2") (pinfunction "2_2") (pintype "passive"))
    )
    (net (code "55") (name "/VBB") (class "Default")
      (node (ref "C86") (pin "1") (pinfunction "1_1") (pintype "passive"))
      (node (ref "C87") (pin "1") (pinfunction "1_1") (pintype "passive"))
      (node (ref "C89") (pin "1") (pinfunction "1_1") (pintype "passive"))
      (node (ref "C90") (pin "1") (pinfunction "1_1") (pintype "passive"))
      (node (ref "C92") (pin "1") (pinfunction "1_1") (pintype "passive"))
      (node (ref "C93") (pin "1") (pinfunction "1_1") (pintype "passive"))
      (node (ref "C95") (pin "1") (pinfunction "1_1") (pintype "passive"))
      (node (ref "C96") (pin "1") (pinfunction "1_1") (pintype "passive"))
      (node (ref "C98") (pin "1") (pinfunction "1_1") (pintype "passive"))
      (node (ref "C99") (pin "1") (pinfunction "1_1") (pintype "passive"))
      (node (ref "JP12") (pin "8") (pinfunction "VBB_8") (pintype "passive"))
      (node (ref "JP15") (pin "8") (pinfunction "VBB_8") (pintype "passive"))
      (node (ref "JP18") (pin "8") (pinfunction "VBB_8") (pintype "passive"))
      (node (ref "JP7") (pin "8") (pinfunction "VBB_8") (pintype "passive"))
      (node (ref "JP9") (pin "8") (pinfunction "VBB_8") (pintype "passive"))
    )
    (net (code "56") (name "/X_MAX") (class "Default")
      (node (ref "C79") (pin "1") (pinfunction "1_1") (pintype "passive"))
      (node (ref "IC1") (pin "39") (pinfunction "P1[25]/MC1A/MAT1[1]_39") (pintype "passive"))
      (node (ref "R95") (pin "2") (pinfunction "2_2") (pintype "passive"))
    )
    (net (code "57") (name "/X_MIN") (class "Default")
      (node (ref "C78") (pin "1") (pinfunction "1_1") (pintype "passive"))
      (node (ref "IC1") (pin "38") (pinfunction "P1[24]/MCFB2/PWM1[5]/MOSI0_38") (pintype "passive"))
      (node (ref "R92") (pin "2") (pinfunction "2_2") (pintype "passive"))
    )
    (net (code "58") (name "/Y_MAX") (class "Default")
      (node (ref "C81") (pin "1") (pinfunction "1_1") (pintype "passive"))
      (node (ref "IC1") (pin "43") (pinfunction "P1[27]/CLKOUT/USB_OVRCR/CAP0[1]_43") (pintype "passive"))
      (node (ref "R99") (pin "2") (pinfunction "2_2") (pintype "passive"))
    )
    (net (code "59") (name "/Y_MIN") (class "Default")
      (node (ref "C80") (pin "1") (pinfunction "1_1") (pintype "passive"))
      (node (ref "IC1") (pin "40") (pinfunction "P1[26]/MC1B/PWM1[6]/CAP0[0]_40") (pintype "passive"))
      (node (ref "R97") (pin "2") (pinfunction "2_2") (pintype "passive"))
    )
    (net (code "60") (name "/Z_MAX") (class "Default")
      (node (ref "C83") (pin "1") (pinfunction "1_1") (pintype "passive"))
      (node (ref "IC1") (pin "45") (pinfunction "P1[29]/MC2B/PCAP1[1]/MAT0[1]_45") (pintype "passive"))
      (node (ref "R103") (pin "2") (pinfunction "2_2") (pintype "passive"))
    )
    (net (code "61") (name "/Z_MIN") (class "Default")
      (node (ref "C82") (pin "1") (pinfunction "1_1") (pintype "passive"))
      (node (ref "IC1") (pin "44") (pinfunction "P1[28]/MC2A/PCAP1[0]/MAT0[0]_44") (pintype "passive"))
      (node (ref "R101") (pin "2") (pinfunction "2_2") (pintype "passive"))
    )
    (net (code "62") (name "3.3V") (class "Default")
      (node (ref "C1") (pin "2") (pinfunction "2_2") (pintype "passive"))
      (node (ref "C10") (pin "2") (pinfunction "2_2") (pintype "passive"))
      (node (ref "C11") (pin "2") (pinfunction "2_2") (pintype "passive"))
      (node (ref "C12") (pin "2") (pinfunction "2_2") (pintype "passive"))
      (node (ref "C13") (pin "2") (pinfunction "2_2") (pintype "passive"))
      (node (ref "C14") (pin "2") (pinfunction "2_2") (pintype "passive"))
      (node (ref "C31") (pin "2") (pinfunction "2_2") (pintype "passive"))
      (node (ref "C67") (pin "2") (pinfunction "2_2") (pintype "passive"))
      (node (ref "C68") (pin "2") (pinfunction "2_2") (pintype "passive"))
      (node (ref "C7") (pin "A") (pinfunction "+_A") (pintype "passive"))
      (node (ref "C8") (pin "2") (pinfunction "2_2") (pintype "passive"))
      (node (ref "C85") (pin "1") (pinfunction "1_1") (pintype "passive"))
      (node (ref "C88") (pin "1") (pinfunction "1_1") (pintype "passive"))
      (node (ref "C9") (pin "2") (pinfunction "2_2") (pintype "passive"))
      (node (ref "C91") (pin "1") (pinfunction "1_1") (pintype "passive"))
      (node (ref "C94") (pin "1") (pinfunction "1_1") (pintype "passive"))
      (node (ref "C97") (pin "1") (pinfunction "1_1") (pintype "passive"))
      (node (ref "IC1") (pin "10") (pinfunction "VDDA_10") (pintype "passive"))
      (node (ref "IC1") (pin "12") (pinfunction "VREFP_12") (pintype "passive"))
      (node (ref "IC1") (pin "19") (pinfunction "VBAT_19") (pintype "passive"))
      (node (ref "IC1") (pin "28") (pinfunction "VDD(3V3)1_28") (pintype "passive"))
      (node (ref "IC1") (pin "42") (pinfunction "VDD(REG)(3V3)1_42") (pintype "passive"))
      (node (ref "IC1") (pin "54") (pinfunction "VDD(3V3)2_54") (pintype "passive"))
      (node (ref "IC1") (pin "71") (pinfunction "VDD(3V3)3_71") (pintype "passive"))
      (node (ref "IC1") (pin "84") (pinfunction "VDD(REG)(3V3)2_84") (pintype "passive"))
      (node (ref "IC1") (pin "96") (pinfunction "VDD(3V3)4_96") (pintype "passive"))
      (node (ref "IC4") (pin "17") (pinfunction "VDD_17") (pintype "passive"))
      (node (ref "IC9") (pin "17") (pinfunction "VDD_17") (pintype "passive"))
      (node (ref "IC9") (pin "4") (pinfunction "HVC/A0_4") (pintype "passive"))
      (node (ref "JP12") (pin "2") (pinfunction "3.3V_2") (pintype "passive"))
      (node (ref "JP122") (pin "1") (pinfunction "1_1") (pintype "passive"))
      (node (ref "JP123") (pin "1") (pinfunction "1_1") (pintype "passive"))
      (node (ref "JP15") (pin "2") (pinfunction "3.3V_2") (pintype "passive"))
      (node (ref "JP152") (pin "1") (pinfunction "1_1") (pintype "passive"))
      (node (ref "JP153") (pin "1") (pinfunction "1_1") (pintype "passive"))
      (node (ref "JP18") (pin "2") (pinfunction "3.3V_2") (pintype "passive"))
      (node (ref "JP182") (pin "1") (pinfunction "1_1") (pintype "passive"))
      (node (ref "JP183") (pin "1") (pinfunction "1_1") (pintype "passive"))
      (node (ref "JP7") (pin "2") (pinfunction "3.3V_2") (pintype "passive"))
      (node (ref "JP72") (pin "1") (pinfunction "1_1") (pintype "passive"))
      (node (ref "JP73") (pin "1") (pinfunction "1_1") (pintype "passive"))
      (node (ref "JP9") (pin "2") (pinfunction "3.3V_2") (pintype "passive"))
      (node (ref "JP92") (pin "1") (pinfunction "1_1") (pintype "passive"))
      (node (ref "JP93") (pin "1") (pinfunction "1_1") (pintype "passive"))
      (node (ref "Q1") (pin "4") (pinfunction "S_4") (pintype "passive"))
      (node (ref "R1") (pin "2") (pinfunction "2_2") (pintype "passive"))
      (node (ref "R14") (pin "2") (pinfunction "2_2") (pintype "passive"))
      (node (ref "R15") (pin "2") (pinfunction "2_2") (pintype "passive"))
      (node (ref "R16") (pin "2") (pinfunction "2_2") (pintype "passive"))
      (node (ref "R17") (pin "1") (pinfunction "1_1") (pintype "passive"))
      (node (ref "R18") (pin "2") (pinfunction "2_2") (pintype "passive"))
      (node (ref "R2") (pin "2") (pinfunction "2_2") (pintype "passive"))
      (node (ref "R3") (pin "2") (pinfunction "2_2") (pintype "passive"))
      (node (ref "R30") (pin "2") (pinfunction "2_2") (pintype "passive"))
      (node (ref "R35") (pin "2") (pinfunction "2_2") (pintype "passive"))
      (node (ref "R36") (pin "2") (pinfunction "2_2") (pintype "passive"))
      (node (ref "R37") (pin "2") (pinfunction "2_2") (pintype "passive"))
      (node (ref "R4") (pin "2") (pinfunction "2_2") (pintype "passive"))
      (node (ref "S6") (pin "2") (pinfunction "2_2") (pintype "passive"))
      (node (ref "U1") (pin "4") (pinfunction "VCC_4") (pintype "passive"))
    )
    (net (code "63") (name "5V") (class "Default")
      (node (ref "JP14") (pin "1") (pinfunction "1_1") (pintype "passive"))
      (node (ref "JP16") (pin "1") (pinfunction "1_1") (pintype "passive"))
      (node (ref "JP19") (pin "1") (pinfunction "1_1") (pintype "passive"))
      (node (ref "JP21") (pin "1") (pinfunction "1_1") (pintype "passive"))
      (node (ref "JP22") (pin "1") (pinfunction "1_1") (pintype "passive"))
      (node (ref "JP26") (pin "1") (pinfunction "1_1") (pintype "passive"))
      (node (ref "R100") (pin "2") (pinfunction "2_2") (pintype "passive"))
      (node (ref "R102") (pin "2") (pinfunction "2_2") (pintype "passive"))
      (node (ref "R93") (pin "2") (pinfunction "2_2") (pintype "passive"))
      (node (ref "R94") (pin "2") (pinfunction "2_2") (pintype "passive"))
      (node (ref "R96") (pin "2") (pinfunction "2_2") (pintype "passive"))
      (node (ref "R98") (pin "2") (pinfunction "2_2") (pintype "passive"))
    )
    (net (code "64") (name "GND") (class "Default")
      (node (ref "C1") (pin "1") (pinfunction "1_1") (pintype "passive"))
      (node (ref "C10") (pin "1") (pinfunction "1_1") (pintype "passive"))
      (node (ref "C11") (pin "1") (pinfunction "1_1") (pintype "passive"))
      (node (ref "C12") (pin "1") (pinfunction "1_1") (pintype "passive"))
      (node (ref "C13") (pin "1") (pinfunction "1_1") (pintype "passive"))
      (node (ref "C14") (pin "1") (pinfunction "1_1") (pintype "passive"))
      (node (ref "C2") (pin "2") (pinfunction "2_2") (pintype "passive"))
      (node (ref "C3") (pin "2") (pinfunction "2_2") (pintype "passive"))
      (node (ref "C31") (pin "1") (pinfunction "1_1") (pintype "passive"))
      (node (ref "C4") (pin "1") (pinfunction "1_1") (pintype "passive"))
      (node (ref "C5") (pin "1") (pinfunction "1_1") (pintype "passive"))
      (node (ref "C67") (pin "1") (pinfunction "1_1") (pintype "passive"))
      (node (ref "C68") (pin "1") (pinfunction "1_1") (pintype "passive"))
      (node (ref "C7") (pin "C") (pinfunction "-_C") (pintype "passive"))
      (node (ref "C78") (pin "2") (pinfunction "2_2") (pintype "passive"))
      (node (ref "C79") (pin "2") (pinfunction "2_2") (pintype "passive"))
      (node (ref "C8") (pin "1") (pinfunction "1_1") (pintype "passive"))
      (node (ref "C80") (pin "2") (pinfunction "2_2") (pintype "passive"))
      (node (ref "C81") (pin "2") (pinfunction "2_2") (pintype "passive"))
      (node (ref "C82") (pin "2") (pinfunction "2_2") (pintype "passive"))
      (node (ref "C83") (pin "2") (pinfunction "2_2") (pintype "passive"))
      (node (ref "C85") (pin "2") (pinfunction "2_2") (pintype "passive"))
      (node (ref "C86") (pin "2") (pinfunction "2_2") (pintype "passive"))
      (node (ref "C87") (pin "2") (pinfunction "2_2") (pintype "passive"))
      (node (ref "C88") (pin "2") (pinfunction "2_2") (pintype "passive"))
      (node (ref "C89") (pin "2") (pinfunction "2_2") (pintype "passive"))
      (node (ref "C9") (pin "1") (pinfunction "1_1") (pintype "passive"))
      (node (ref "C90") (pin "2") (pinfunction "2_2") (pintype "passive"))
      (node (ref "C91") (pin "2") (pinfunction "2_2") (pintype "passive"))
      (node (ref "C92") (pin "2") (pinfunction "2_2") (pintype "passive"))
      (node (ref "C93") (pin "2") (pinfunction "2_2") (pintype "passive"))
      (node (ref "C94") (pin "2") (pinfunction "2_2") (pintype "passive"))
      (node (ref "C95") (pin "2") (pinfunction "2_2") (pintype "passive"))
      (node (ref "C96") (pin "2") (pinfunction "2_2") (pintype "passive"))
      (node (ref "C97") (pin "2") (pinfunction "2_2") (pintype "passive"))
      (node (ref "C98") (pin "2") (pinfunction "2_2") (pintype "passive"))
      (node (ref "C99") (pin "2") (pinfunction "2_2") (pintype "passive"))
      (node (ref "IC1") (pin "11") (pinfunction "VSSA_11") (pintype "passive"))
      (node (ref "IC1") (pin "15") (pinfunction "VREFN_15") (pintype "passive"))
      (node (ref "IC1") (pin "31") (pinfunction "VSS1_31") (pintype "passive"))
      (node (ref "IC1") (pin "41") (pinfunction "VSS2_41") (pintype "passive"))
      (node (ref "IC1") (pin "55") (pinfunction "VSS3_55") (pintype "passive"))
      (node (ref "IC1") (pin "72") (pinfunction "VSS4_72") (pintype "passive"))
      (node (ref "IC1") (pin "83") (pinfunction "VSS6_83") (pintype "passive"))
      (node (ref "IC1") (pin "97") (pinfunction "VSS5_97") (pintype "passive"))
      (node (ref "IC4") (pin "13") (pinfunction "P0B_13") (pintype "passive"))
      (node (ref "IC4") (pin "16") (pinfunction "A1_16") (pintype "passive"))
      (node (ref "IC4") (pin "18") (pinfunction "P2B_18") (pintype "passive"))
      (node (ref "IC4") (pin "3") (pinfunction "P3B_3") (pintype "passive"))
      (node (ref "IC4") (pin "4") (pinfunction "HVC/A0_4") (pintype "passive"))
      (node (ref "IC4") (pin "7") (pinfunction "VSS_7") (pintype "passive"))
      (node (ref "IC4") (pin "8") (pinfunction "P1B_8") (pintype "passive"))
      (node (ref "IC9") (pin "13") (pinfunction "P0B_13") (pintype "passive"))
      (node (ref "IC9") (pin "16") (pinfunction "A1_16") (pintype "passive"))
      (node (ref "IC9") (pin "18") (pinfunction "P2B_18") (pintype "passive"))
      (node (ref "IC9") (pin "3") (pinfunction "P3B_3") (pintype "passive"))
      (node (ref "IC9") (pin "7") (pinfunction "VSS_7") (pintype "passive"))
      (node (ref "IC9") (pin "8") (pinfunction "P1B_8") (pintype "passive"))
      (node (ref "JP12") (pin "1") (pinfunction "GND_1") (pintype "passive"))
      (node (ref "JP12") (pin "7") (pinfunction "GND_7") (pintype "passive"))
      (node (ref "JP122") (pin "3") (pinfunction "3_3") (pintype "passive"))
      (node (ref "JP123") (pin "3") (pinfunction "3_3") (pintype "passive"))
      (node (ref "JP14") (pin "2") (pinfunction "2_2") (pintype "passive"))
      (node (ref "JP15") (pin "1") (pinfunction "GND_1") (pintype "passive"))
      (node (ref "JP15") (pin "7") (pinfunction "GND_7") (pintype "passive"))
      (node (ref "JP152") (pin "3") (pinfunction "3_3") (pintype "passive"))
      (node (ref "JP153") (pin "3") (pinfunction "3_3") (pintype "passive"))
      (node (ref "JP16") (pin "2") (pinfunction "2_2") (pintype "passive"))
      (node (ref "JP18") (pin "1") (pinfunction "GND_1") (pintype "passive"))
      (node (ref "JP18") (pin "7") (pinfunction "GND_7") (pintype "passive"))
      (node (ref "JP182") (pin "3") (pinfunction "3_3") (pintype "passive"))
      (node (ref "JP183") (pin "3") (pinfunction "3_3") (pintype "passive"))
      (node (ref "JP19") (pin "2") (pinfunction "2_2") (pintype "passive"))
      (node (ref "JP21") (pin "2") (pinfunction "2_2") (pintype "passive"))
      (node (ref "JP22") (pin "2") (pinfunction "2_2") (pintype "passive"))
      (node (ref "JP23") (pin "2") (pinfunction "2_2") (pintype "passive"))
      (node (ref "JP26") (pin "2") (pinfunction "2_2") (pintype "passive"))
      (node (ref "JP7") (pin "1") (pinfunction "GND_1") (pintype "passive"))
      (node (ref "JP7") (pin "7") (pinfunction "GND_7") (pintype "passive"))
      (node (ref "JP72") (pin "3") (pinfunction "3_3") (pintype "passive"))
      (node (ref "JP73") (pin "3") (pinfunction "3_3") (pintype "passive"))
      (node (ref "JP9") (pin "1") (pinfunction "GND_1") (pintype "passive"))
      (node (ref "JP9") (pin "7") (pinfunction "GND_7") (pintype "passive"))
      (node (ref "JP92") (pin "3") (pinfunction "3_3") (pintype "passive"))
      (node (ref "JP93") (pin "3") (pinfunction "3_3") (pintype "passive"))
      (node (ref "LED1") (pin "1") (pinfunction "1_1") (pintype "passive"))
      (node (ref "LED2") (pin "1") (pinfunction "1_1") (pintype "passive"))
      (node (ref "LED3") (pin "1") (pinfunction "1_1") (pintype "passive"))
      (node (ref "LED4") (pin "1") (pinfunction "1_1") (pintype "passive"))
      (node (ref "S1") (pin "2") (pinfunction "2_2") (pintype "passive"))
      (node (ref "S2") (pin "2") (pinfunction "2_2") (pintype "passive"))
      (node (ref "S3") (pin "2") (pinfunction "2_2") (pintype "passive"))
      (node (ref "S6") (pin "1") (pinfunction "1_1") (pintype "passive"))
      (node (ref "U1") (pin "6") (pinfunction "GND_6") (pintype "passive"))
      (node (ref "U1") (pin "CD2") (pinfunction "SHIELD_CD2") (pintype "passive"))
      (node (ref "U1") (pin "GND1") (pinfunction "SHIELD_GND1") (pintype "passive"))
      (node (ref "X14") (pin "GND") (pinfunction "GND_GND") (pintype "passive"))
    )
    (net (code "65") (name "Net-(IC1-XTAL1)") (class "Default")
      (node (ref "C2") (pin "1") (pinfunction "1_1") (pintype "passive"))
      (node (ref "IC1") (pin "22") (pinfunction "XTAL1_22") (pintype "passive"))
      (node (ref "Q2") (pin "3") (pinfunction "3_3") (pintype "passive"))
    )
    (net (code "66") (name "Net-(IC1-XTAL2)") (class "Default")
      (node (ref "C3") (pin "1") (pinfunction "1_1") (pintype "passive"))
      (node (ref "IC1") (pin "23") (pinfunction "XTAL2_23") (pintype "passive"))
      (node (ref "Q2") (pin "1") (pinfunction "1_1") (pintype "passive"))
    )
    (net (code "67") (name "Net-(IC4-!RESET)") (class "Default")
      (node (ref "IC4") (pin "15") (pinfunction "!RESET_15") (pintype "passive"))
      (node (ref "R37") (pin "1") (pinfunction "1_1") (pintype "passive"))
    )
    (net (code "68") (name "Net-(IC4-P0A)") (class "Default")
      (node (ref "IC4") (pin "1") (pinfunction "P3A_1") (pintype "passive"))
      (node (ref "IC4") (pin "10") (pinfunction "P1A_10") (pintype "passive"))
      (node (ref "IC4") (pin "11") (pinfunction "P0A_11") (pintype "passive"))
      (node (ref "IC4") (pin "20") (pinfunction "P2A_20") (pintype "passive"))
      (node (ref "R30") (pin "1") (pinfunction "1_1") (pintype "passive"))
    )
    (net (code "69") (name "Net-(IC9-!RESET)") (class "Default")
      (node (ref "IC9") (pin "15") (pinfunction "!RESET_15") (pintype "passive"))
      (node (ref "R4") (pin "1") (pinfunction "1_1") (pintype "passive"))
    )
    (net (code "70") (name "Net-(IC9-P0A)") (class "Default")
      (node (ref "IC9") (pin "1") (pinfunction "P3A_1") (pintype "passive"))
      (node (ref "IC9") (pin "10") (pinfunction "P1A_10") (pintype "passive"))
      (node (ref "IC9") (pin "11") (pinfunction "P0A_11") (pintype "passive"))
      (node (ref "IC9") (pin "20") (pinfunction "P2A_20") (pintype "passive"))
      (node (ref "R18") (pin "1") (pinfunction "1_1") (pintype "passive"))
    )
    (net (code "71") (name "Net-(JP7-1A)") (class "Default")
      (node (ref "JP7") (pin "4") (pinfunction "1A_4") (pintype "passive"))
      (node (ref "M1") (pin "2") (pinfunction "2_2") (pintype "passive"))
    )
    (net (code "72") (name "Net-(JP7-1B)") (class "Default")
      (node (ref "JP7") (pin "3") (pinfunction "1B_3") (pintype "passive"))
      (node (ref "M1") (pin "1") (pinfunction "1_1") (pintype "passive"))
    )
    (net (code "73") (name "Net-(JP7-2A)") (class "Default")
      (node (ref "JP7") (pin "5") (pinfunction "2A_5") (pintype "passive"))
      (node (ref "M1") (pin "3") (pinfunction "3_3") (pintype "passive"))
    )
    (net (code "74") (name "Net-(JP7-2B)") (class "Default")
      (node (ref "JP7") (pin "6") (pinfunction "2B_6") (pintype "passive"))
      (node (ref "M1") (pin "4") (pinfunction "4_4") (pintype "passive"))
    )
    (net (code "75") (name "Net-(JP9-1A)") (class "Default")
      (node (ref "JP9") (pin "4") (pinfunction "1A_4") (pintype "passive"))
      (node (ref "M2") (pin "2") (pinfunction "2_2") (pintype "passive"))
    )
    (net (code "76") (name "Net-(JP9-1B)") (class "Default")
      (node (ref "JP9") (pin "3") (pinfunction "1B_3") (pintype "passive"))
      (node (ref "M2") (pin "1") (pinfunction "1_1") (pintype "passive"))
    )
    (net (code "77") (name "Net-(JP9-2A)") (class "Default")
      (node (ref "JP9") (pin "5") (pinfunction "2A_5") (pintype "passive"))
      (node (ref "M2") (pin "3") (pinfunction "3_3") (pintype "passive"))
    )
    (net (code "78") (name "Net-(JP9-2B)") (class "Default")
      (node (ref "JP9") (pin "6") (pinfunction "2B_6") (pintype "passive"))
      (node (ref "M2") (pin "4") (pinfunction "4_4") (pintype "passive"))
    )
    (net (code "79") (name "Net-(JP12-1A)") (class "Default")
      (node (ref "JP12") (pin "4") (pinfunction "1A_4") (pintype "passive"))
      (node (ref "M3") (pin "2") (pinfunction "2_2") (pintype "passive"))
    )
    (net (code "80") (name "Net-(JP12-1B)") (class "Default")
      (node (ref "JP12") (pin "3") (pinfunction "1B_3") (pintype "passive"))
      (node (ref "M3") (pin "1") (pinfunction "1_1") (pintype "passive"))
    )
    (net (code "81") (name "Net-(JP12-2A)") (class "Default")
      (node (ref "JP12") (pin "5") (pinfunction "2A_5") (pintype "passive"))
      (node (ref "M3") (pin "3") (pinfunction "3_3") (pintype "passive"))
    )
    (net (code "82") (name "Net-(JP12-2B)") (class "Default")
      (node (ref "JP12") (pin "6") (pinfunction "2B_6") (pintype "passive"))
      (node (ref "M3") (pin "4") (pinfunction "4_4") (pintype "passive"))
    )
    (net (code "83") (name "Net-(JP14-Pad3)") (class "Default")
      (node (ref "JP14") (pin "3") (pinfunction "3_3") (pintype "passive"))
      (node (ref "R94") (pin "1") (pinfunction "1_1") (pintype "passive"))
      (node (ref "R95") (pin "1") (pinfunction "1_1") (pintype "passive"))
    )
    (net (code "84") (name "Net-(JP15-1A)") (class "Default")
      (node (ref "JP15") (pin "4") (pinfunction "1A_4") (pintype "passive"))
      (node (ref "M4") (pin "2") (pinfunction "2_2") (pintype "passive"))
    )
    (net (code "85") (name "Net-(JP15-1B)") (class "Default")
      (node (ref "JP15") (pin "3") (pinfunction "1B_3") (pintype "passive"))
      (node (ref "M4") (pin "1") (pinfunction "1_1") (pintype "passive"))
    )
    (net (code "86") (name "Net-(JP15-2A)") (class "Default")
      (node (ref "JP15") (pin "5") (pinfunction "2A_5") (pintype "passive"))
      (node (ref "M4") (pin "3") (pinfunction "3_3") (pintype "passive"))
    )
    (net (code "87") (name "Net-(JP15-2B)") (class "Default")
      (node (ref "JP15") (pin "6") (pinfunction "2B_6") (pintype "passive"))
      (node (ref "M4") (pin "4") (pinfunction "4_4") (pintype "passive"))
    )
    (net (code "88") (name "Net-(JP16-Pad3)") (class "Default")
      (node (ref "JP16") (pin "3") (pinfunction "3_3") (pintype "passive"))
      (node (ref "R96") (pin "1") (pinfunction "1_1") (pintype "passive"))
      (node (ref "R97") (pin "1") (pinfunction "1_1") (pintype "passive"))
    )
    (net (code "89") (name "Net-(JP18-1A)") (class "Default")
      (node (ref "JP18") (pin "4") (pinfunction "1A_4") (pintype "passive"))
      (node (ref "M5") (pin "2") (pinfunction "2_2") (pintype "passive"))
    )
    (net (code "90") (name "Net-(JP18-1B)") (class "Default")
      (node (ref "JP18") (pin "3") (pinfunction "1B_3") (pintype "passive"))
      (node (ref "M5") (pin "1") (pinfunction "1_1") (pintype "passive"))
    )
    (net (code "91") (name "Net-(JP18-2A)") (class "Default")
      (node (ref "JP18") (pin "5") (pinfunction "2A_5") (pintype "passive"))
      (node (ref "M5") (pin "3") (pinfunction "3_3") (pintype "passive"))
    )
    (net (code "92") (name "Net-(JP18-2B)") (class "Default")
      (node (ref "JP18") (pin "6") (pinfunction "2B_6") (pintype "passive"))
      (node (ref "M5") (pin "4") (pinfunction "4_4") (pintype "passive"))
    )
    (net (code "93") (name "Net-(JP19-Pad3)") (class "Default")
      (node (ref "JP19") (pin "3") (pinfunction "3_3") (pintype "passive"))
      (node (ref "R98") (pin "1") (pinfunction "1_1") (pintype "passive"))
      (node (ref "R99") (pin "1") (pinfunction "1_1") (pintype "passive"))
    )
    (net (code "94") (name "Net-(JP21-Pad3)") (class "Default")
      (node (ref "JP21") (pin "3") (pinfunction "3_3") (pintype "passive"))
      (node (ref "R100") (pin "1") (pinfunction "1_1") (pintype "passive"))
      (node (ref "R101") (pin "1") (pinfunction "1_1") (pintype "passive"))
    )
    (net (code "95") (name "Net-(JP22-Pad3)") (class "Default")
      (node (ref "JP22") (pin "3") (pinfunction "3_3") (pintype "passive"))
      (node (ref "R102") (pin "1") (pinfunction "1_1") (pintype "passive"))
      (node (ref "R103") (pin "1") (pinfunction "1_1") (pintype "passive"))
    )
    (net (code "96") (name "Net-(JP24-Pad1)") (class "Default")
      (node (ref "JP24") (pin "1") (pinfunction "1_1") (pintype "passive"))
      (node (ref "R17") (pin "2") (pinfunction "2_2") (pintype "passive"))
      (node (ref "S3") (pin "C") (pinfunction "C_C") (pintype "passive"))
    )
    (net (code "97") (name "Net-(JP26-Pad3)") (class "Default")
      (node (ref "JP26") (pin "3") (pinfunction "3_3") (pintype "passive"))
      (node (ref "R92") (pin "1") (pinfunction "1_1") (pintype "passive"))
      (node (ref "R93") (pin "1") (pinfunction "1_1") (pintype "passive"))
    )
    (net (code "98") (name "Net-(LED1-Pad2)") (class "Default")
      (node (ref "LED1") (pin "2") (pinfunction "2_2") (pintype "passive"))
      (node (ref "R10") (pin "1") (pinfunction "1_1") (pintype "passive"))
    )
    (net (code "99") (name "Net-(LED2-Pad2)") (class "Default")
      (node (ref "LED2") (pin "2") (pinfunction "2_2") (pintype "passive"))
      (node (ref "R11") (pin "1") (pinfunction "1_1") (pintype "passive"))
    )
    (net (code "100") (name "Net-(LED3-Pad2)") (class "Default")
      (node (ref "LED3") (pin "2") (pinfunction "2_2") (pintype "passive"))
      (node (ref "R12") (pin "1") (pinfunction "1_1") (pintype "passive"))
    )
    (net (code "101") (name "Net-(LED4-Pad2)") (class "Default")
      (node (ref "LED4") (pin "2") (pinfunction "2_2") (pintype "passive"))
      (node (ref "R13") (pin "1") (pinfunction "1_1") (pintype "passive"))
    )
    (net (code "102") (name "Net-(Q1-D-Pad1)") (class "Default")
      (node (ref "Q1") (pin "1") (pinfunction "D_1") (pintype "passive"))
      (node (ref "Q1") (pin "2") (pinfunction "D_2") (pintype "passive"))
      (node (ref "Q1") (pin "5") (pinfunction "D_5") (pintype "passive"))
      (node (ref "Q1") (pin "6") (pinfunction "D_6") (pintype "passive"))
      (node (ref "R7") (pin "2") (pinfunction "2_2") (pintype "passive"))
    )
    (net (code "103") (name "Net-(R8-Pad1)") (class "Default")
      (node (ref "R8") (pin "1") (pinfunction "1_1") (pintype "passive"))
      (node (ref "X14") (pin "D+") (pinfunction "D+_D+") (pintype "passive"))
    )
    (net (code "104") (name "Net-(R9-Pad1)") (class "Default")
      (node (ref "R9") (pin "1") (pinfunction "1_1") (pintype "passive"))
      (node (ref "X14") (pin "D-") (pinfunction "D-_D-") (pintype "passive"))
    )
    (net (code "105") (name "VUSB") (class "Default")
      (node (ref "X14") (pin "VBUS") (pinfunction "VBUS_VBUS") (pintype "passive"))
    )
    (net (code "106") (name "unconnected-(H1-Pad1)") (class "Default")
      (node (ref "H1") (pin "1") (pinfunction "1_1") (pintype "passive"))
    )
    (net (code "107") (name "unconnected-(H1-Pad2)") (class "Default")
      (node (ref "H1") (pin "2") (pinfunction "2_2") (pintype "passive"))
    )
    (net (code "108") (name "unconnected-(H2-Pad1)") (class "Default")
      (node (ref "H2") (pin "1") (pinfunction "1_1") (pintype "passive"))
    )
    (net (code "109") (name "unconnected-(H2-Pad2)") (class "Default")
      (node (ref "H2") (pin "2") (pinfunction "2_2") (pintype "passive"))
    )
    (net (code "110") (name "unconnected-(H3-Pad1)") (class "Default")
      (node (ref "H3") (pin "1") (pinfunction "1_1") (pintype "passive"))
    )
    (net (code "111") (name "unconnected-(H3-Pad2)") (class "Default")
      (node (ref "H3") (pin "2") (pinfunction "2_2") (pintype "passive"))
    )
    (net (code "112") (name "unconnected-(H4-Pad1)") (class "Default")
      (node (ref "H4") (pin "1") (pinfunction "1_1") (pintype "passive"))
    )
    (net (code "113") (name "unconnected-(H4-Pad2)") (class "Default")
      (node (ref "H4") (pin "2") (pinfunction "2_2") (pintype "passive"))
    )
    (net (code "114") (name "unconnected-(H5-Pad1)") (class "Default")
      (node (ref "H5") (pin "1") (pinfunction "1_1") (pintype "passive"))
    )
    (net (code "115") (name "unconnected-(H5-Pad2)") (class "Default")
      (node (ref "H5") (pin "2") (pinfunction "2_2") (pintype "passive"))
    )
    (net (code "116") (name "unconnected-(IC1-N.C.-Pad13)") (class "Default")
      (node (ref "IC1") (pin "13") (pinfunction "N.C._13") (pintype "passive"))
    )
    (net (code "117") (name "unconnected-(IC1-P0[15]{slash}TXD1{slash}SCK0{slash}SCK-Pad62)") (class "Default")
      (node (ref "IC1") (pin "62") (pinfunction "P0[15]/TXD1/SCK0/SCK_62") (pintype "passive"))
    )
    (net (code "118") (name "unconnected-(IC1-P0[16]{slash}RXD1{slash}SSEL0{slash}SSEL-Pad63)") (class "Default")
      (node (ref "IC1") (pin "63") (pinfunction "P0[16]/RXD1/SSEL0/SSEL_63") (pintype "passive"))
    )
    (net (code "119") (name "unconnected-(IC1-P0[17]{slash}CTS1{slash}MISO0{slash}MISO-Pad61)") (class "Default")
      (node (ref "IC1") (pin "61") (pinfunction "P0[17]/CTS1/MISO0/MISO_61") (pintype "passive"))
    )
    (net (code "120") (name "unconnected-(IC1-P0[18]{slash}DCD1{slash}MOSI0{slash}MOSI-Pad60)") (class "Default")
      (node (ref "IC1") (pin "60") (pinfunction "P0[18]/DCD1/MOSI0/MOSI_60") (pintype "passive"))
    )
    (net (code "121") (name "unconnected-(IC1-P0[23]{slash}AD0[0]{slash}I2SRX_CLK{slash}CAP3[0]-Pad9)") (class "Default")
      (node (ref "IC1") (pin "9") (pinfunction "P0[23]/AD0[0]/I2SRX_CLK/CAP3[0]_9") (pintype "passive"))
    )
    (net (code "122") (name "unconnected-(IC1-P0[24]{slash}AD0[1]{slash}I2SRX_WS{slash}CAP3[1]-Pad8)") (class "Default")
      (node (ref "IC1") (pin "8") (pinfunction "P0[24]/AD0[1]/I2SRX_WS/CAP3[1]_8") (pintype "passive"))
    )
    (net (code "123") (name "unconnected-(IC1-P0[25]{slash}AD0[2]{slash}I2SRX_SDA{slash}TXD3-Pad7)") (class "Default")
      (node (ref "IC1") (pin "7") (pinfunction "P0[25]/AD0[2]/I2SRX_SDA/TXD3_7") (pintype "passive"))
    )
    (net (code "124") (name "unconnected-(IC1-P0[26]{slash}AD0[3]{slash}AOUT{slash}RXD3-Pad6)") (class "Default")
      (node (ref "IC1") (pin "6") (pinfunction "P0[26]/AD0[3]/AOUT/RXD3_6") (pintype "passive"))
    )
    (net (code "125") (name "unconnected-(IC1-P0[27]{slash}SDA0{slash}USB_SDA-Pad25)") (class "Default")
      (node (ref "IC1") (pin "25") (pinfunction "P0[27]/SDA0/USB_SDA_25") (pintype "passive"))
    )
    (net (code "126") (name "unconnected-(IC1-P0[28]{slash}SCL0{slash}USB_SCL-Pad24)") (class "Default")
      (node (ref "IC1") (pin "24") (pinfunction "P0[28]/SCL0/USB_SCL_24") (pintype "passive"))
    )
    (net (code "127") (name "unconnected-(IC1-P1[0]{slash}ENET_TXD0-Pad95)") (class "Default")
      (node (ref "IC1") (pin "95") (pinfunction "P1[0]/ENET_TXD0_95") (pintype "passive"))
    )
    (net (code "128") (name "unconnected-(IC1-P1[1]{slash}ENET_TXD1-Pad94)") (class "Default")
      (node (ref "IC1") (pin "94") (pinfunction "P1[1]/ENET_TXD1_94") (pintype "passive"))
    )
    (net (code "129") (name "unconnected-(IC1-P1[4]{slash}ENET_TX_EN-Pad93)") (class "Default")
      (node (ref "IC1") (pin "93") (pinfunction "P1[4]/ENET_TX_EN_93") (pintype "passive"))
    )
    (net (code "130") (name "unconnected-(IC1-P1[8]{slash}ENET_CRS-Pad92)") (class "Default")
      (node (ref "IC1") (pin "92") (pinfunction "P1[8]/ENET_CRS_92") (pintype "passive"))
    )
    (net (code "131") (name "unconnected-(IC1-P1[9]{slash}ENET_RXD0-Pad91)") (class "Default")
      (node (ref "IC1") (pin "91") (pinfunction "P1[9]/ENET_RXD0_91") (pintype "passive"))
    )
    (net (code "132") (name "unconnected-(IC1-P1[10]{slash}ENET_RXD1-Pad90)") (class "Default")
      (node (ref "IC1") (pin "90") (pinfunction "P1[10]/ENET_RXD1_90") (pintype "passive"))
    )
    (net (code "133") (name "unconnected-(IC1-P1[14]{slash}ENET_RX_ER-Pad89)") (class "Default")
      (node (ref "IC1") (pin "89") (pinfunction "P1[14]/ENET_RX_ER_89") (pintype "passive"))
    )
    (net (code "134") (name "unconnected-(IC1-P1[15]{slash}ENET_REF_CLK-Pad88)") (class "Default")
      (node (ref "IC1") (pin "88") (pinfunction "P1[15]/ENET_REF_CLK_88") (pintype "passive"))
    )
    (net (code "135") (name "unconnected-(IC1-P1[16]{slash}ENET_MDC-Pad87)") (class "Default")
      (node (ref "IC1") (pin "87") (pinfunction "P1[16]/ENET_MDC_87") (pintype "passive"))
    )
    (net (code "136") (name "unconnected-(IC1-P1[17]{slash}ENET_MDIO-Pad86)") (class "Default")
      (node (ref "IC1") (pin "86") (pinfunction "P1[17]/ENET_MDIO_86") (pintype "passive"))
    )
    (net (code "137") (name "unconnected-(IC1-P1[30]{slash}VBUS{slash}AD0[4]-Pad21)") (class "Default")
      (node (ref "IC1") (pin "21") (pinfunction "P1[30]/VBUS/AD0[4]_21") (pintype "passive"))
    )
    (net (code "138") (name "unconnected-(IC1-P1[31]{slash}SCK1{slash}AD0[5]-Pad20)") (class "Default")
      (node (ref "IC1") (pin "20") (pinfunction "P1[31]/SCK1/AD0[5]_20") (pintype "passive"))
    )
    (net (code "139") (name "unconnected-(IC1-P2[6]{slash}PCAP1[0]{slash}RI1{slash}TRACECLK-Pad67)") (class "Default")
      (node (ref "IC1") (pin "67") (pinfunction "P2[6]/PCAP1[0]/RI1/TRACECLK_67") (pintype "passive"))
    )
    (net (code "140") (name "unconnected-(IC1-P2[11]{slash}EINT1{slash}I2STX_CLK-Pad52)") (class "Default")
      (node (ref "IC1") (pin "52") (pinfunction "P2[11]/EINT1/I2STX_CLK_52") (pintype "passive"))
    )
    (net (code "141") (name "unconnected-(IC1-P3[25]{slash}MAT0[0]{slash}PWM1[2]-Pad27)") (class "Default")
      (node (ref "IC1") (pin "27") (pinfunction "P3[25]/MAT0[0]/PWM1[2]_27") (pintype "passive"))
    )
    (net (code "142") (name "unconnected-(IC1-P3[26]{slash}STCLK{slash}MAT0[1]{slash}PWM1[3]-Pad26)") (class "Default")
      (node (ref "IC1") (pin "26") (pinfunction "P3[26]/STCLK/MAT0[1]/PWM1[3]_26") (pintype "passive"))
    )
    (net (code "143") (name "unconnected-(IC1-RSTOUT-Pad14)") (class "Default")
      (node (ref "IC1") (pin "14") (pinfunction "RSTOUT_14") (pintype "passive"))
    )
    (net (code "144") (name "unconnected-(IC1-RTCK-Pad100)") (class "Default")
      (node (ref "IC1") (pin "100") (pinfunction "RTCK_100") (pintype "passive"))
    )
    (net (code "145") (name "unconnected-(IC1-RTCX1-Pad16)") (class "Default")
      (node (ref "IC1") (pin "16") (pinfunction "RTCX1_16") (pintype "passive"))
    )
    (net (code "146") (name "unconnected-(IC1-RTCX2-Pad18)") (class "Default")
      (node (ref "IC1") (pin "18") (pinfunction "RTCX2_18") (pintype "passive"))
    )
    (net (code "147") (name "unconnected-(IC1-TCK{slash}SWDCLK-Pad5)") (class "Default")
      (node (ref "IC1") (pin "5") (pinfunction "TCK/SWDCLK_5") (pintype "passive"))
    )
    (net (code "148") (name "unconnected-(IC1-TDI-Pad2)") (class "Default")
      (node (ref "IC1") (pin "2") (pinfunction "TDI_2") (pintype "passive"))
    )
    (net (code "149") (name "unconnected-(IC1-TDO{slash}SWO-Pad1)") (class "Default")
      (node (ref "IC1") (pin "1") (pinfunction "TDO/SWO_1") (pintype "passive"))
    )
    (net (code "150") (name "unconnected-(IC1-TMS{slash}SWDIO-Pad3)") (class "Default")
      (node (ref "IC1") (pin "3") (pinfunction "TMS/SWDIO_3") (pintype "passive"))
    )
    (net (code "151") (name "unconnected-(IC1-TRST-Pad4)") (class "Default")
      (node (ref "IC1") (pin "4") (pinfunction "TRST_4") (pintype "passive"))
    )
    (net (code "152") (name "unconnected-(IC4-NC-Pad14)") (class "Default")
      (node (ref "IC4") (pin "14") (pinfunction "NC_14") (pintype "passive"))
    )
    (net (code "153") (name "unconnected-(IC9-NC-Pad14)") (class "Default")
      (node (ref "IC9") (pin "14") (pinfunction "NC_14") (pintype "passive"))
    )
    (net (code "154") (name "unconnected-(IC9-P1W-Pad9)") (class "Default")
      (node (ref "IC9") (pin "9") (pinfunction "P1W_9") (pintype "passive"))
    )
    (net (code "155") (name "unconnected-(IC9-P2W-Pad19)") (class "Default")
      (node (ref "IC9") (pin "19") (pinfunction "P2W_19") (pintype "passive"))
    )
    (net (code "156") (name "unconnected-(IC9-P3W-Pad2)") (class "Default")
      (node (ref "IC9") (pin "2") (pinfunction "P3W_2") (pintype "passive"))
    )
    (net (code "157") (name "unconnected-(JP71-1A-Pad4)") (class "Default")
      (node (ref "JP71") (pin "4") (pinfunction "1A_4") (pintype "passive"))
    )
    (net (code "158") (name "unconnected-(JP71-2A-Pad5)") (class "Default")
      (node (ref "JP71") (pin "5") (pinfunction "2A_5") (pintype "passive"))
    )
    (net (code "159") (name "unconnected-(JP71-2B-Pad6)") (class "Default")
      (node (ref "JP71") (pin "6") (pinfunction "2B_6") (pintype "passive"))
    )
    (net (code "160") (name "unconnected-(JP71-GND-Pad7)") (class "Default")
      (node (ref "JP71") (pin "7") (pinfunction "GND_7") (pintype "passive"))
    )
    (net (code "161") (name "unconnected-(JP72-Pad2)") (class "Default")
      (node (ref "JP72") (pin "2") (pinfunction "2_2") (pintype "passive"))
    )
    (net (code "162") (name "unconnected-(JP73-Pad2)") (class "Default")
      (node (ref "JP73") (pin "2") (pinfunction "2_2") (pintype "passive"))
    )
    (net (code "163") (name "unconnected-(JP91-1A-Pad4)") (class "Default")
      (node (ref "JP91") (pin "4") (pinfunction "1A_4") (pintype "passive"))
    )
    (net (code "164") (name "unconnected-(JP91-2A-Pad5)") (class "Default")
      (node (ref "JP91") (pin "5") (pinfunction "2A_5") (pintype "passive"))
    )
    (net (code "165") (name "unconnected-(JP91-2B-Pad6)") (class "Default")
      (node (ref "JP91") (pin "6") (pinfunction "2B_6") (pintype "passive"))
    )
    (net (code "166") (name "unconnected-(JP91-GND-Pad7)") (class "Default")
      (node (ref "JP91") (pin "7") (pinfunction "GND_7") (pintype "passive"))
    )
    (net (code "167") (name "unconnected-(JP92-Pad2)") (class "Default")
      (node (ref "JP92") (pin "2") (pinfunction "2_2") (pintype "passive"))
    )
    (net (code "168") (name "unconnected-(JP93-Pad2)") (class "Default")
      (node (ref "JP93") (pin "2") (pinfunction "2_2") (pintype "passive"))
    )
    (net (code "169") (name "unconnected-(JP121-1A-Pad4)") (class "Default")
      (node (ref "JP121") (pin "4") (pinfunction "1A_4") (pintype "passive"))
    )
    (net (code "170") (name "unconnected-(JP121-2A-Pad5)") (class "Default")
      (node (ref "JP121") (pin "5") (pinfunction "2A_5") (pintype "passive"))
    )
    (net (code "171") (name "unconnected-(JP121-2B-Pad6)") (class "Default")
      (node (ref "JP121") (pin "6") (pinfunction "2B_6") (pintype "passive"))
    )
    (net (code "172") (name "unconnected-(JP121-GND-Pad7)") (class "Default")
      (node (ref "JP121") (pin "7") (pinfunction "GND_7") (pintype "passive"))
    )
    (net (code "173") (name "unconnected-(JP122-Pad2)") (class "Default")
      (node (ref "JP122") (pin "2") (pinfunction "2_2") (pintype "passive"))
    )
    (net (code "174") (name "unconnected-(JP123-Pad2)") (class "Default")
      (node (ref "JP123") (pin "2") (pinfunction "2_2") (pintype "passive"))
    )
    (net (code "175") (name "unconnected-(JP151-1A-Pad4)") (class "Default")
      (node (ref "JP151") (pin "4") (pinfunction "1A_4") (pintype "passive"))
    )
    (net (code "176") (name "unconnected-(JP151-2A-Pad5)") (class "Default")
      (node (ref "JP151") (pin "5") (pinfunction "2A_5") (pintype "passive"))
    )
    (net (code "177") (name "unconnected-(JP151-2B-Pad6)") (class "Default")
      (node (ref "JP151") (pin "6") (pinfunction "2B_6") (pintype "passive"))
    )
    (net (code "178") (name "unconnected-(JP151-GND-Pad7)") (class "Default")
      (node (ref "JP151") (pin "7") (pinfunction "GND_7") (pintype "passive"))
    )
    (net (code "179") (name "unconnected-(JP152-Pad2)") (class "Default")
      (node (ref "JP152") (pin "2") (pinfunction "2_2") (pintype "passive"))
    )
    (net (code "180") (name "unconnected-(JP153-Pad2)") (class "Default")
      (node (ref "JP153") (pin "2") (pinfunction "2_2") (pintype "passive"))
    )
    (net (code "181") (name "unconnected-(JP181-1A-Pad4)") (class "Default")
      (node (ref "JP181") (pin "4") (pinfunction "1A_4") (pintype "passive"))
    )
    (net (code "182") (name "unconnected-(JP181-2A-Pad5)") (class "Default")
      (node (ref "JP181") (pin "5") (pinfunction "2A_5") (pintype "passive"))
    )
    (net (code "183") (name "unconnected-(JP181-2B-Pad6)") (class "Default")
      (node (ref "JP181") (pin "6") (pinfunction "2B_6") (pintype "passive"))
    )
    (net (code "184") (name "unconnected-(JP181-GND-Pad7)") (class "Default")
      (node (ref "JP181") (pin "7") (pinfunction "GND_7") (pintype "passive"))
    )
    (net (code "185") (name "unconnected-(JP182-Pad2)") (class "Default")
      (node (ref "JP182") (pin "2") (pinfunction "2_2") (pintype "passive"))
    )
    (net (code "186") (name "unconnected-(JP183-Pad2)") (class "Default")
      (node (ref "JP183") (pin "2") (pinfunction "2_2") (pintype "passive"))
    )
    (net (code "187") (name "unconnected-(U1-NC-Pad1)") (class "Default")
      (node (ref "U1") (pin "1") (pinfunction "NC_1") (pintype "passive"))
    )
    (net (code "188") (name "unconnected-(U1-RSV-Pad8)") (class "Default")
      (node (ref "U1") (pin "8") (pinfunction "RSV_8") (pintype "passive"))
    )
    (net (code "189") (name "unconnected-(U1-SHIELD-PadCD1)") (class "Default")
      (node (ref "U1") (pin "CD1") (pinfunction "SHIELD_CD1") (pintype "passive"))
    )
    (net (code "190") (name "unconnected-(U1-SHIELD-PadGND3)") (class "Default")
      (node (ref "U1") (pin "GND3") (pinfunction "SHIELD_GND3") (pintype "passive"))
    )
  )
)
